# SOC_level_indicator.net
KiCad netlist of a schematic drawn in EAGLE
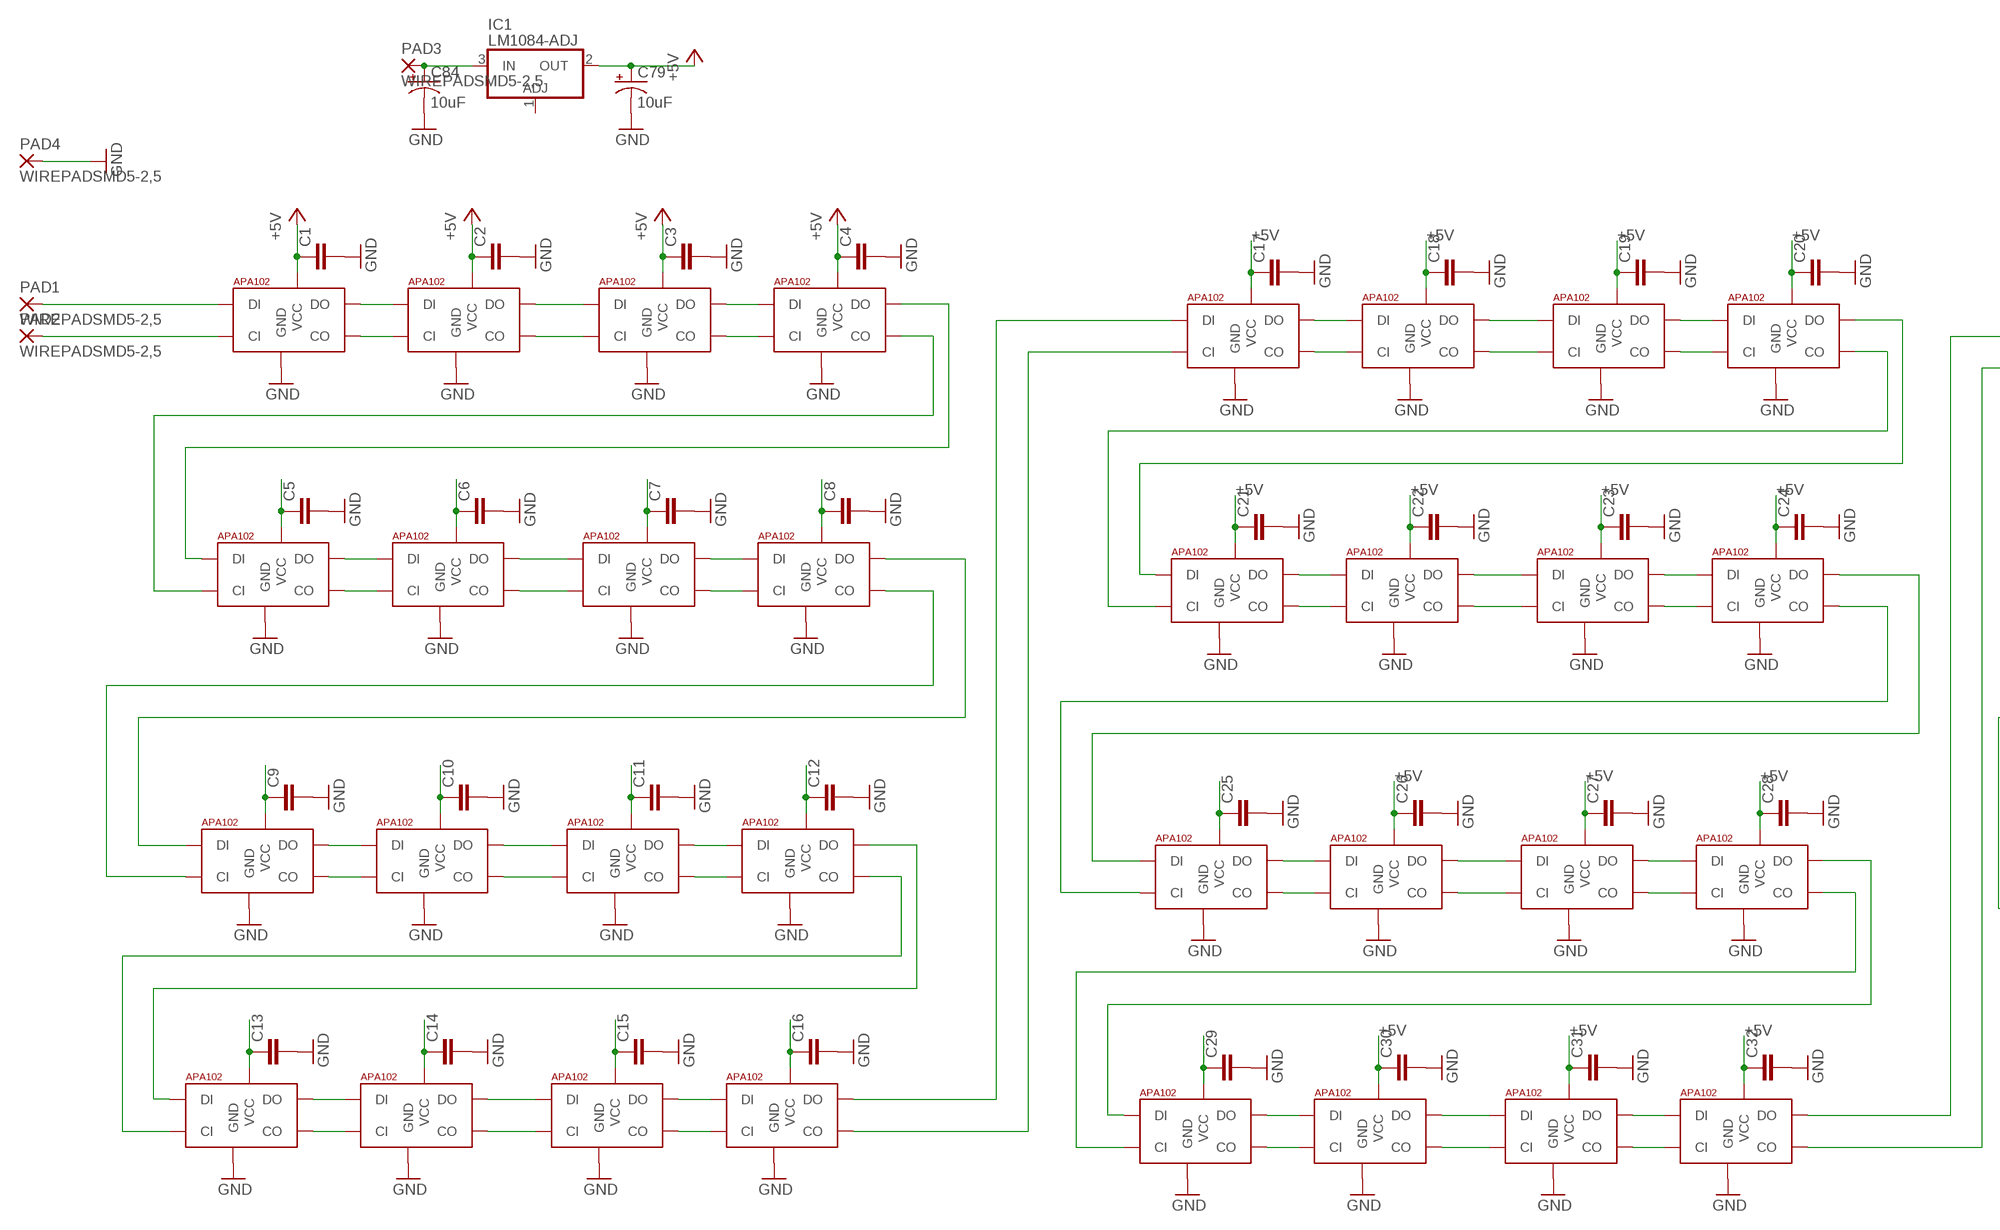
[diagram p0: schematic, sheet 1, part 1 of 2]
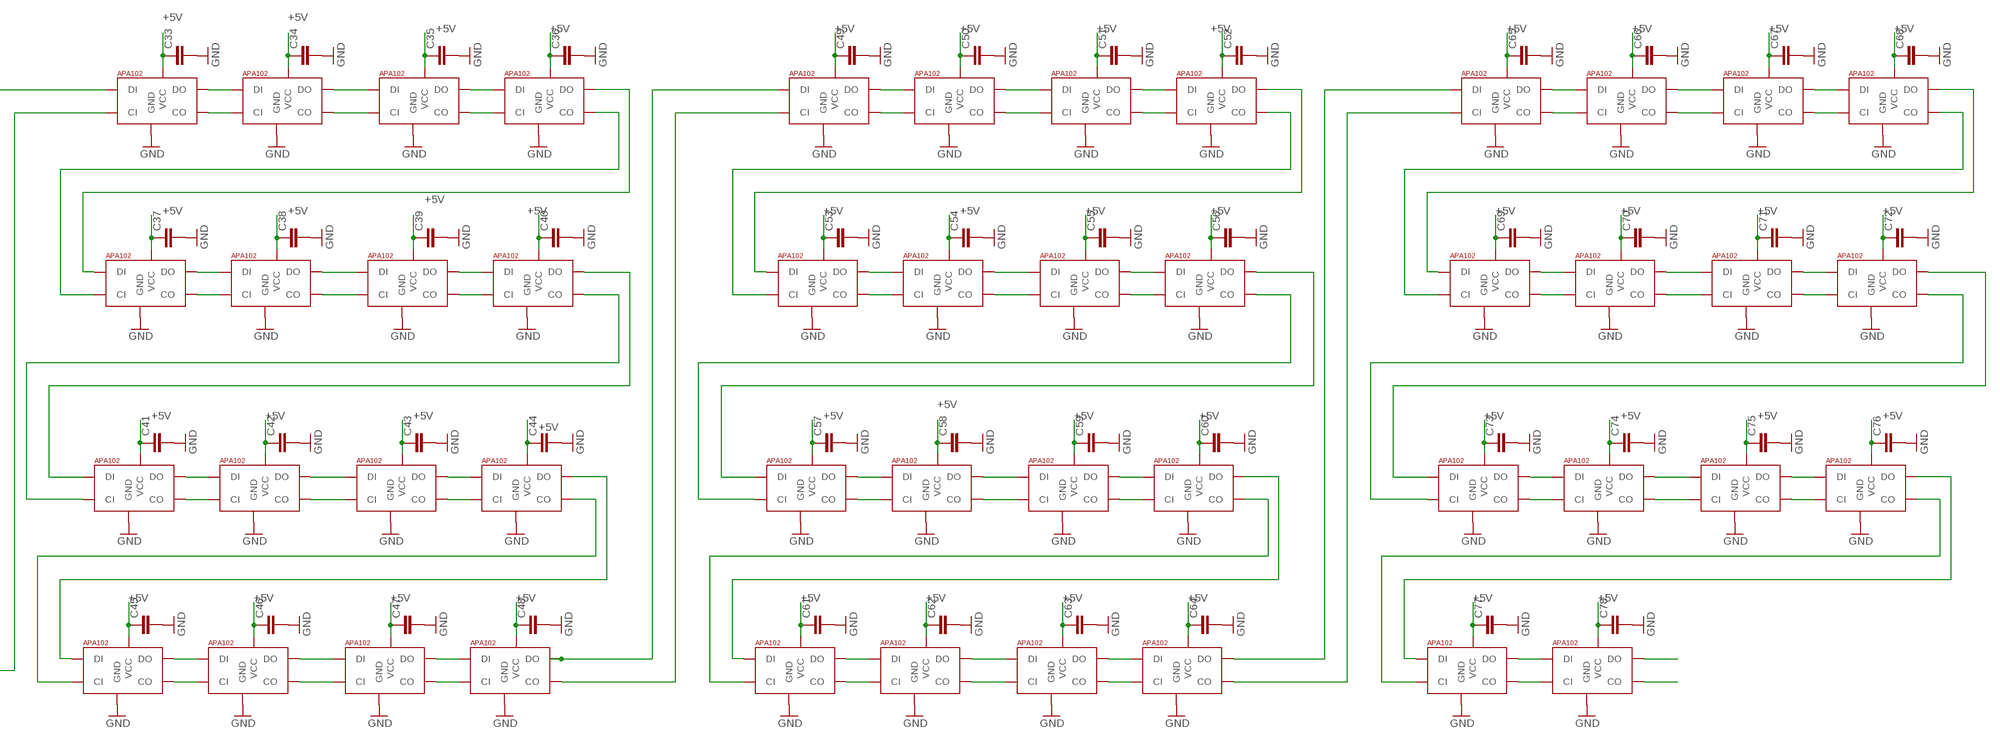
[diagram p1: schematic, sheet 1, part 2 of 2]

(export (version "E")
  (design (tool "Eeschema 10.0.6"))
  (components
    (comp (ref "C1")
      (value "CAP0603-CAP")
      (footprint "eagle-import:0603-CAP")
      (libsource (lib "eagle-import") (part "CAP0603-CAP"))
    )
    (comp (ref "C2")
      (value "CAP0603-CAP")
      (footprint "eagle-import:0603-CAP")
      (libsource (lib "eagle-import") (part "CAP0603-CAP"))
    )
    (comp (ref "C3")
      (value "CAP0603-CAP")
      (footprint "eagle-import:0603-CAP")
      (libsource (lib "eagle-import") (part "CAP0603-CAP"))
    )
    (comp (ref "C4")
      (value "CAP0603-CAP")
      (footprint "eagle-import:0603-CAP")
      (libsource (lib "eagle-import") (part "CAP0603-CAP"))
    )
    (comp (ref "C5")
      (value "CAP0603-CAP")
      (footprint "eagle-import:0603-CAP")
      (libsource (lib "eagle-import") (part "CAP0603-CAP"))
    )
    (comp (ref "C6")
      (value "CAP0603-CAP")
      (footprint "eagle-import:0603-CAP")
      (libsource (lib "eagle-import") (part "CAP0603-CAP"))
    )
    (comp (ref "C7")
      (value "CAP0603-CAP")
      (footprint "eagle-import:0603-CAP")
      (libsource (lib "eagle-import") (part "CAP0603-CAP"))
    )
    (comp (ref "C8")
      (value "CAP0603-CAP")
      (footprint "eagle-import:0603-CAP")
      (libsource (lib "eagle-import") (part "CAP0603-CAP"))
    )
    (comp (ref "C9")
      (value "CAP0603-CAP")
      (footprint "eagle-import:0603-CAP")
      (libsource (lib "eagle-import") (part "CAP0603-CAP"))
    )
    (comp (ref "C10")
      (value "CAP0603-CAP")
      (footprint "eagle-import:0603-CAP")
      (libsource (lib "eagle-import") (part "CAP0603-CAP"))
    )
    (comp (ref "C11")
      (value "CAP0603-CAP")
      (footprint "eagle-import:0603-CAP")
      (libsource (lib "eagle-import") (part "CAP0603-CAP"))
    )
    (comp (ref "C12")
      (value "CAP0603-CAP")
      (footprint "eagle-import:0603-CAP")
      (libsource (lib "eagle-import") (part "CAP0603-CAP"))
    )
    (comp (ref "C13")
      (value "CAP0603-CAP")
      (footprint "eagle-import:0603-CAP")
      (libsource (lib "eagle-import") (part "CAP0603-CAP"))
    )
    (comp (ref "C14")
      (value "CAP0603-CAP")
      (footprint "eagle-import:0603-CAP")
      (libsource (lib "eagle-import") (part "CAP0603-CAP"))
    )
    (comp (ref "C15")
      (value "CAP0603-CAP")
      (footprint "eagle-import:0603-CAP")
      (libsource (lib "eagle-import") (part "CAP0603-CAP"))
    )
    (comp (ref "C16")
      (value "CAP0603-CAP")
      (footprint "eagle-import:0603-CAP")
      (libsource (lib "eagle-import") (part "CAP0603-CAP"))
    )
    (comp (ref "C17")
      (value "CAP0603-CAP")
      (footprint "eagle-import:0603-CAP")
      (libsource (lib "eagle-import") (part "CAP0603-CAP"))
    )
    (comp (ref "C18")
      (value "CAP0603-CAP")
      (footprint "eagle-import:0603-CAP")
      (libsource (lib "eagle-import") (part "CAP0603-CAP"))
    )
    (comp (ref "C19")
      (value "CAP0603-CAP")
      (footprint "eagle-import:0603-CAP")
      (libsource (lib "eagle-import") (part "CAP0603-CAP"))
    )
    (comp (ref "C20")
      (value "CAP0603-CAP")
      (footprint "eagle-import:0603-CAP")
      (libsource (lib "eagle-import") (part "CAP0603-CAP"))
    )
    (comp (ref "C21")
      (value "CAP0603-CAP")
      (footprint "eagle-import:0603-CAP")
      (libsource (lib "eagle-import") (part "CAP0603-CAP"))
    )
    (comp (ref "C22")
      (value "CAP0603-CAP")
      (footprint "eagle-import:0603-CAP")
      (libsource (lib "eagle-import") (part "CAP0603-CAP"))
    )
    (comp (ref "C23")
      (value "CAP0603-CAP")
      (footprint "eagle-import:0603-CAP")
      (libsource (lib "eagle-import") (part "CAP0603-CAP"))
    )
    (comp (ref "C24")
      (value "CAP0603-CAP")
      (footprint "eagle-import:0603-CAP")
      (libsource (lib "eagle-import") (part "CAP0603-CAP"))
    )
    (comp (ref "C25")
      (value "CAP0603-CAP")
      (footprint "eagle-import:0603-CAP")
      (libsource (lib "eagle-import") (part "CAP0603-CAP"))
    )
    (comp (ref "C26")
      (value "CAP0603-CAP")
      (footprint "eagle-import:0603-CAP")
      (libsource (lib "eagle-import") (part "CAP0603-CAP"))
    )
    (comp (ref "C27")
      (value "CAP0603-CAP")
      (footprint "eagle-import:0603-CAP")
      (libsource (lib "eagle-import") (part "CAP0603-CAP"))
    )
    (comp (ref "C28")
      (value "CAP0603-CAP")
      (footprint "eagle-import:0603-CAP")
      (libsource (lib "eagle-import") (part "CAP0603-CAP"))
    )
    (comp (ref "C29")
      (value "CAP0603-CAP")
      (footprint "eagle-import:0603-CAP")
      (libsource (lib "eagle-import") (part "CAP0603-CAP"))
    )
    (comp (ref "C30")
      (value "CAP0603-CAP")
      (footprint "eagle-import:0603-CAP")
      (libsource (lib "eagle-import") (part "CAP0603-CAP"))
    )
    (comp (ref "C31")
      (value "CAP0603-CAP")
      (footprint "eagle-import:0603-CAP")
      (libsource (lib "eagle-import") (part "CAP0603-CAP"))
    )
    (comp (ref "C32")
      (value "CAP0603-CAP")
      (footprint "eagle-import:0603-CAP")
      (libsource (lib "eagle-import") (part "CAP0603-CAP"))
    )
    (comp (ref "C33")
      (value "CAP0603-CAP")
      (footprint "eagle-import:0603-CAP")
      (libsource (lib "eagle-import") (part "CAP0603-CAP"))
    )
    (comp (ref "C34")
      (value "CAP0603-CAP")
      (footprint "eagle-import:0603-CAP")
      (libsource (lib "eagle-import") (part "CAP0603-CAP"))
    )
    (comp (ref "C35")
      (value "CAP0603-CAP")
      (footprint "eagle-import:0603-CAP")
      (libsource (lib "eagle-import") (part "CAP0603-CAP"))
    )
    (comp (ref "C36")
      (value "CAP0603-CAP")
      (footprint "eagle-import:0603-CAP")
      (libsource (lib "eagle-import") (part "CAP0603-CAP"))
    )
    (comp (ref "C37")
      (value "CAP0603-CAP")
      (footprint "eagle-import:0603-CAP")
      (libsource (lib "eagle-import") (part "CAP0603-CAP"))
    )
    (comp (ref "C38")
      (value "CAP0603-CAP")
      (footprint "eagle-import:0603-CAP")
      (libsource (lib "eagle-import") (part "CAP0603-CAP"))
    )
    (comp (ref "C39")
      (value "CAP0603-CAP")
      (footprint "eagle-import:0603-CAP")
      (libsource (lib "eagle-import") (part "CAP0603-CAP"))
    )
    (comp (ref "C40")
      (value "CAP0603-CAP")
      (footprint "eagle-import:0603-CAP")
      (libsource (lib "eagle-import") (part "CAP0603-CAP"))
    )
    (comp (ref "C41")
      (value "CAP0603-CAP")
      (footprint "eagle-import:0603-CAP")
      (libsource (lib "eagle-import") (part "CAP0603-CAP"))
    )
    (comp (ref "C42")
      (value "CAP0603-CAP")
      (footprint "eagle-import:0603-CAP")
      (libsource (lib "eagle-import") (part "CAP0603-CAP"))
    )
    (comp (ref "C43")
      (value "CAP0603-CAP")
      (footprint "eagle-import:0603-CAP")
      (libsource (lib "eagle-import") (part "CAP0603-CAP"))
    )
    (comp (ref "C44")
      (value "CAP0603-CAP")
      (footprint "eagle-import:0603-CAP")
      (libsource (lib "eagle-import") (part "CAP0603-CAP"))
    )
    (comp (ref "C45")
      (value "CAP0603-CAP")
      (footprint "eagle-import:0603-CAP")
      (libsource (lib "eagle-import") (part "CAP0603-CAP"))
    )
    (comp (ref "C46")
      (value "CAP0603-CAP")
      (footprint "eagle-import:0603-CAP")
      (libsource (lib "eagle-import") (part "CAP0603-CAP"))
    )
    (comp (ref "C47")
      (value "CAP0603-CAP")
      (footprint "eagle-import:0603-CAP")
      (libsource (lib "eagle-import") (part "CAP0603-CAP"))
    )
    (comp (ref "C48")
      (value "CAP0603-CAP")
      (footprint "eagle-import:0603-CAP")
      (libsource (lib "eagle-import") (part "CAP0603-CAP"))
    )
    (comp (ref "C49")
      (value "CAP0603-CAP")
      (footprint "eagle-import:0603-CAP")
      (libsource (lib "eagle-import") (part "CAP0603-CAP"))
    )
    (comp (ref "C50")
      (value "CAP0603-CAP")
      (footprint "eagle-import:0603-CAP")
      (libsource (lib "eagle-import") (part "CAP0603-CAP"))
    )
    (comp (ref "C51")
      (value "CAP0603-CAP")
      (footprint "eagle-import:0603-CAP")
      (libsource (lib "eagle-import") (part "CAP0603-CAP"))
    )
    (comp (ref "C52")
      (value "CAP0603-CAP")
      (footprint "eagle-import:0603-CAP")
      (libsource (lib "eagle-import") (part "CAP0603-CAP"))
    )
    (comp (ref "C53")
      (value "CAP0603-CAP")
      (footprint "eagle-import:0603-CAP")
      (libsource (lib "eagle-import") (part "CAP0603-CAP"))
    )
    (comp (ref "C54")
      (value "CAP0603-CAP")
      (footprint "eagle-import:0603-CAP")
      (libsource (lib "eagle-import") (part "CAP0603-CAP"))
    )
    (comp (ref "C55")
      (value "CAP0603-CAP")
      (footprint "eagle-import:0603-CAP")
      (libsource (lib "eagle-import") (part "CAP0603-CAP"))
    )
    (comp (ref "C56")
      (value "CAP0603-CAP")
      (footprint "eagle-import:0603-CAP")
      (libsource (lib "eagle-import") (part "CAP0603-CAP"))
    )
    (comp (ref "C57")
      (value "CAP0603-CAP")
      (footprint "eagle-import:0603-CAP")
      (libsource (lib "eagle-import") (part "CAP0603-CAP"))
    )
    (comp (ref "C58")
      (value "CAP0603-CAP")
      (footprint "eagle-import:0603-CAP")
      (libsource (lib "eagle-import") (part "CAP0603-CAP"))
    )
    (comp (ref "C59")
      (value "CAP0603-CAP")
      (footprint "eagle-import:0603-CAP")
      (libsource (lib "eagle-import") (part "CAP0603-CAP"))
    )
    (comp (ref "C60")
      (value "CAP0603-CAP")
      (footprint "eagle-import:0603-CAP")
      (libsource (lib "eagle-import") (part "CAP0603-CAP"))
    )
    (comp (ref "C61")
      (value "CAP0603-CAP")
      (footprint "eagle-import:0603-CAP")
      (libsource (lib "eagle-import") (part "CAP0603-CAP"))
    )
    (comp (ref "C62")
      (value "CAP0603-CAP")
      (footprint "eagle-import:0603-CAP")
      (libsource (lib "eagle-import") (part "CAP0603-CAP"))
    )
    (comp (ref "C63")
      (value "CAP0603-CAP")
      (footprint "eagle-import:0603-CAP")
      (libsource (lib "eagle-import") (part "CAP0603-CAP"))
    )
    (comp (ref "C64")
      (value "CAP0603-CAP")
      (footprint "eagle-import:0603-CAP")
      (libsource (lib "eagle-import") (part "CAP0603-CAP"))
    )
    (comp (ref "C65")
      (value "CAP0603-CAP")
      (footprint "eagle-import:0603-CAP")
      (libsource (lib "eagle-import") (part "CAP0603-CAP"))
    )
    (comp (ref "C66")
      (value "CAP0603-CAP")
      (footprint "eagle-import:0603-CAP")
      (libsource (lib "eagle-import") (part "CAP0603-CAP"))
    )
    (comp (ref "C67")
      (value "CAP0603-CAP")
      (footprint "eagle-import:0603-CAP")
      (libsource (lib "eagle-import") (part "CAP0603-CAP"))
    )
    (comp (ref "C68")
      (value "CAP0603-CAP")
      (footprint "eagle-import:0603-CAP")
      (libsource (lib "eagle-import") (part "CAP0603-CAP"))
    )
    (comp (ref "C69")
      (value "CAP0603-CAP")
      (footprint "eagle-import:0603-CAP")
      (libsource (lib "eagle-import") (part "CAP0603-CAP"))
    )
    (comp (ref "C70")
      (value "CAP0603-CAP")
      (footprint "eagle-import:0603-CAP")
      (libsource (lib "eagle-import") (part "CAP0603-CAP"))
    )
    (comp (ref "C71")
      (value "CAP0603-CAP")
      (footprint "eagle-import:0603-CAP")
      (libsource (lib "eagle-import") (part "CAP0603-CAP"))
    )
    (comp (ref "C72")
      (value "CAP0603-CAP")
      (footprint "eagle-import:0603-CAP")
      (libsource (lib "eagle-import") (part "CAP0603-CAP"))
    )
    (comp (ref "C73")
      (value "CAP0603-CAP")
      (footprint "eagle-import:0603-CAP")
      (libsource (lib "eagle-import") (part "CAP0603-CAP"))
    )
    (comp (ref "C74")
      (value "CAP0603-CAP")
      (footprint "eagle-import:0603-CAP")
      (libsource (lib "eagle-import") (part "CAP0603-CAP"))
    )
    (comp (ref "C75")
      (value "CAP0603-CAP")
      (footprint "eagle-import:0603-CAP")
      (libsource (lib "eagle-import") (part "CAP0603-CAP"))
    )
    (comp (ref "C76")
      (value "CAP0603-CAP")
      (footprint "eagle-import:0603-CAP")
      (libsource (lib "eagle-import") (part "CAP0603-CAP"))
    )
    (comp (ref "C77")
      (value "CAP0603-CAP")
      (footprint "eagle-import:0603-CAP")
      (libsource (lib "eagle-import") (part "CAP0603-CAP"))
    )
    (comp (ref "C78")
      (value "CAP0603-CAP")
      (footprint "eagle-import:0603-CAP")
      (libsource (lib "eagle-import") (part "CAP0603-CAP"))
    )
    (comp (ref "C79")
      (value "10uF")
      (footprint "eagle-import:EIA3216")
      (libsource (lib "eagle-import") (part "10UF-16V-10%(TANT)"))
    )
    (comp (ref "C84")
      (value "10uF")
      (footprint "eagle-import:EIA3216")
      (libsource (lib "eagle-import") (part "10UF-16V-10%(TANT)"))
    )
    (comp (ref "IC1")
      (value "LM1084-ADJ")
      (footprint "eagle-import:TO263-3")
      (libsource (lib "eagle-import") (part "LM1084-ADJ"))
    )
    (comp (ref "PAD1")
      (value "WIREPADSMD5-2,5")
      (footprint "eagle-import:5-2,5")
      (libsource (lib "eagle-import") (part "WIREPADSMD5-2,5"))
    )
    (comp (ref "PAD2")
      (value "WIREPADSMD5-2,5")
      (footprint "eagle-import:5-2,5")
      (libsource (lib "eagle-import") (part "WIREPADSMD5-2,5"))
    )
    (comp (ref "PAD3")
      (value "WIREPADSMD5-2,5")
      (footprint "eagle-import:5-2,5")
      (libsource (lib "eagle-import") (part "WIREPADSMD5-2,5"))
    )
    (comp (ref "PAD4")
      (value "WIREPADSMD5-2,5")
      (footprint "eagle-import:5-2,5")
      (libsource (lib "eagle-import") (part "WIREPADSMD5-2,5"))
    )
    (comp (ref "U$1")
      (value "APA1025050")
      (footprint "eagle-import:APA102_5050")
      (libsource (lib "eagle-import") (part "APA1025050"))
    )
    (comp (ref "U$2")
      (value "APA1025050")
      (footprint "eagle-import:APA102_5050")
      (libsource (lib "eagle-import") (part "APA1025050"))
    )
    (comp (ref "U$3")
      (value "APA1025050")
      (footprint "eagle-import:APA102_5050")
      (libsource (lib "eagle-import") (part "APA1025050"))
    )
    (comp (ref "U$4")
      (value "APA1025050")
      (footprint "eagle-import:APA102_5050")
      (libsource (lib "eagle-import") (part "APA1025050"))
    )
    (comp (ref "U$5")
      (value "APA1025050")
      (footprint "eagle-import:APA102_5050")
      (libsource (lib "eagle-import") (part "APA1025050"))
    )
    (comp (ref "U$6")
      (value "APA1025050")
      (footprint "eagle-import:APA102_5050")
      (libsource (lib "eagle-import") (part "APA1025050"))
    )
    (comp (ref "U$7")
      (value "APA1025050")
      (footprint "eagle-import:APA102_5050")
      (libsource (lib "eagle-import") (part "APA1025050"))
    )
    (comp (ref "U$8")
      (value "APA1025050")
      (footprint "eagle-import:APA102_5050")
      (libsource (lib "eagle-import") (part "APA1025050"))
    )
    (comp (ref "U$9")
      (value "APA1025050")
      (footprint "eagle-import:APA102_5050")
      (libsource (lib "eagle-import") (part "APA1025050"))
    )
    (comp (ref "U$10")
      (value "APA1025050")
      (footprint "eagle-import:APA102_5050")
      (libsource (lib "eagle-import") (part "APA1025050"))
    )
    (comp (ref "U$11")
      (value "APA1025050")
      (footprint "eagle-import:APA102_5050")
      (libsource (lib "eagle-import") (part "APA1025050"))
    )
    (comp (ref "U$12")
      (value "APA1025050")
      (footprint "eagle-import:APA102_5050")
      (libsource (lib "eagle-import") (part "APA1025050"))
    )
    (comp (ref "U$13")
      (value "APA1025050")
      (footprint "eagle-import:APA102_5050")
      (libsource (lib "eagle-import") (part "APA1025050"))
    )
    (comp (ref "U$14")
      (value "APA1025050")
      (footprint "eagle-import:APA102_5050")
      (libsource (lib "eagle-import") (part "APA1025050"))
    )
    (comp (ref "U$15")
      (value "APA1025050")
      (footprint "eagle-import:APA102_5050")
      (libsource (lib "eagle-import") (part "APA1025050"))
    )
    (comp (ref "U$16")
      (value "APA1025050")
      (footprint "eagle-import:APA102_5050")
      (libsource (lib "eagle-import") (part "APA1025050"))
    )
    (comp (ref "U$17")
      (value "APA1025050")
      (footprint "eagle-import:APA102_5050")
      (libsource (lib "eagle-import") (part "APA1025050"))
    )
    (comp (ref "U$18")
      (value "APA1025050")
      (footprint "eagle-import:APA102_5050")
      (libsource (lib "eagle-import") (part "APA1025050"))
    )
    (comp (ref "U$19")
      (value "APA1025050")
      (footprint "eagle-import:APA102_5050")
      (libsource (lib "eagle-import") (part "APA1025050"))
    )
    (comp (ref "U$20")
      (value "APA1025050")
      (footprint "eagle-import:APA102_5050")
      (libsource (lib "eagle-import") (part "APA1025050"))
    )
    (comp (ref "U$21")
      (value "APA1025050")
      (footprint "eagle-import:APA102_5050")
      (libsource (lib "eagle-import") (part "APA1025050"))
    )
    (comp (ref "U$22")
      (value "APA1025050")
      (footprint "eagle-import:APA102_5050")
      (libsource (lib "eagle-import") (part "APA1025050"))
    )
    (comp (ref "U$23")
      (value "APA1025050")
      (footprint "eagle-import:APA102_5050")
      (libsource (lib "eagle-import") (part "APA1025050"))
    )
    (comp (ref "U$24")
      (value "APA1025050")
      (footprint "eagle-import:APA102_5050")
      (libsource (lib "eagle-import") (part "APA1025050"))
    )
    (comp (ref "U$25")
      (value "APA1025050")
      (footprint "eagle-import:APA102_5050")
      (libsource (lib "eagle-import") (part "APA1025050"))
    )
    (comp (ref "U$26")
      (value "APA1025050")
      (footprint "eagle-import:APA102_5050")
      (libsource (lib "eagle-import") (part "APA1025050"))
    )
    (comp (ref "U$27")
      (value "APA1025050")
      (footprint "eagle-import:APA102_5050")
      (libsource (lib "eagle-import") (part "APA1025050"))
    )
    (comp (ref "U$28")
      (value "APA1025050")
      (footprint "eagle-import:APA102_5050")
      (libsource (lib "eagle-import") (part "APA1025050"))
    )
    (comp (ref "U$29")
      (value "APA1025050")
      (footprint "eagle-import:APA102_5050")
      (libsource (lib "eagle-import") (part "APA1025050"))
    )
    (comp (ref "U$30")
      (value "APA1025050")
      (footprint "eagle-import:APA102_5050")
      (libsource (lib "eagle-import") (part "APA1025050"))
    )
    (comp (ref "U$31")
      (value "APA1025050")
      (footprint "eagle-import:APA102_5050")
      (libsource (lib "eagle-import") (part "APA1025050"))
    )
    (comp (ref "U$32")
      (value "APA1025050")
      (footprint "eagle-import:APA102_5050")
      (libsource (lib "eagle-import") (part "APA1025050"))
    )
    (comp (ref "U$33")
      (value "APA1025050")
      (footprint "eagle-import:APA102_5050")
      (libsource (lib "eagle-import") (part "APA1025050"))
    )
    (comp (ref "U$34")
      (value "APA1025050")
      (footprint "eagle-import:APA102_5050")
      (libsource (lib "eagle-import") (part "APA1025050"))
    )
    (comp (ref "U$35")
      (value "APA1025050")
      (footprint "eagle-import:APA102_5050")
      (libsource (lib "eagle-import") (part "APA1025050"))
    )
    (comp (ref "U$36")
      (value "APA1025050")
      (footprint "eagle-import:APA102_5050")
      (libsource (lib "eagle-import") (part "APA1025050"))
    )
    (comp (ref "U$37")
      (value "APA1025050")
      (footprint "eagle-import:APA102_5050")
      (libsource (lib "eagle-import") (part "APA1025050"))
    )
    (comp (ref "U$38")
      (value "APA1025050")
      (footprint "eagle-import:APA102_5050")
      (libsource (lib "eagle-import") (part "APA1025050"))
    )
    (comp (ref "U$39")
      (value "APA1025050")
      (footprint "eagle-import:APA102_5050")
      (libsource (lib "eagle-import") (part "APA1025050"))
    )
    (comp (ref "U$40")
      (value "APA1025050")
      (footprint "eagle-import:APA102_5050")
      (libsource (lib "eagle-import") (part "APA1025050"))
    )
    (comp (ref "U$41")
      (value "APA1025050")
      (footprint "eagle-import:APA102_5050")
      (libsource (lib "eagle-import") (part "APA1025050"))
    )
    (comp (ref "U$42")
      (value "APA1025050")
      (footprint "eagle-import:APA102_5050")
      (libsource (lib "eagle-import") (part "APA1025050"))
    )
    (comp (ref "U$43")
      (value "APA1025050")
      (footprint "eagle-import:APA102_5050")
      (libsource (lib "eagle-import") (part "APA1025050"))
    )
    (comp (ref "U$44")
      (value "APA1025050")
      (footprint "eagle-import:APA102_5050")
      (libsource (lib "eagle-import") (part "APA1025050"))
    )
    (comp (ref "U$45")
      (value "APA1025050")
      (footprint "eagle-import:APA102_5050")
      (libsource (lib "eagle-import") (part "APA1025050"))
    )
    (comp (ref "U$46")
      (value "APA1025050")
      (footprint "eagle-import:APA102_5050")
      (libsource (lib "eagle-import") (part "APA1025050"))
    )
    (comp (ref "U$47")
      (value "APA1025050")
      (footprint "eagle-import:APA102_5050")
      (libsource (lib "eagle-import") (part "APA1025050"))
    )
    (comp (ref "U$48")
      (value "APA1025050")
      (footprint "eagle-import:APA102_5050")
      (libsource (lib "eagle-import") (part "APA1025050"))
    )
    (comp (ref "U$49")
      (value "APA1025050")
      (footprint "eagle-import:APA102_5050")
      (libsource (lib "eagle-import") (part "APA1025050"))
    )
    (comp (ref "U$50")
      (value "APA1025050")
      (footprint "eagle-import:APA102_5050")
      (libsource (lib "eagle-import") (part "APA1025050"))
    )
    (comp (ref "U$51")
      (value "APA1025050")
      (footprint "eagle-import:APA102_5050")
      (libsource (lib "eagle-import") (part "APA1025050"))
    )
    (comp (ref "U$52")
      (value "APA1025050")
      (footprint "eagle-import:APA102_5050")
      (libsource (lib "eagle-import") (part "APA1025050"))
    )
    (comp (ref "U$53")
      (value "APA1025050")
      (footprint "eagle-import:APA102_5050")
      (libsource (lib "eagle-import") (part "APA1025050"))
    )
    (comp (ref "U$54")
      (value "APA1025050")
      (footprint "eagle-import:APA102_5050")
      (libsource (lib "eagle-import") (part "APA1025050"))
    )
    (comp (ref "U$55")
      (value "APA1025050")
      (footprint "eagle-import:APA102_5050")
      (libsource (lib "eagle-import") (part "APA1025050"))
    )
    (comp (ref "U$56")
      (value "APA1025050")
      (footprint "eagle-import:APA102_5050")
      (libsource (lib "eagle-import") (part "APA1025050"))
    )
    (comp (ref "U$57")
      (value "APA1025050")
      (footprint "eagle-import:APA102_5050")
      (libsource (lib "eagle-import") (part "APA1025050"))
    )
    (comp (ref "U$58")
      (value "APA1025050")
      (footprint "eagle-import:APA102_5050")
      (libsource (lib "eagle-import") (part "APA1025050"))
    )
    (comp (ref "U$59")
      (value "APA1025050")
      (footprint "eagle-import:APA102_5050")
      (libsource (lib "eagle-import") (part "APA1025050"))
    )
    (comp (ref "U$60")
      (value "APA1025050")
      (footprint "eagle-import:APA102_5050")
      (libsource (lib "eagle-import") (part "APA1025050"))
    )
    (comp (ref "U$61")
      (value "APA1025050")
      (footprint "eagle-import:APA102_5050")
      (libsource (lib "eagle-import") (part "APA1025050"))
    )
    (comp (ref "U$62")
      (value "APA1025050")
      (footprint "eagle-import:APA102_5050")
      (libsource (lib "eagle-import") (part "APA1025050"))
    )
    (comp (ref "U$63")
      (value "APA1025050")
      (footprint "eagle-import:APA102_5050")
      (libsource (lib "eagle-import") (part "APA1025050"))
    )
    (comp (ref "U$64")
      (value "APA1025050")
      (footprint "eagle-import:APA102_5050")
      (libsource (lib "eagle-import") (part "APA1025050"))
    )
    (comp (ref "U$65")
      (value "APA1025050")
      (footprint "eagle-import:APA102_5050")
      (libsource (lib "eagle-import") (part "APA1025050"))
    )
    (comp (ref "U$66")
      (value "APA1025050")
      (footprint "eagle-import:APA102_5050")
      (libsource (lib "eagle-import") (part "APA1025050"))
    )
    (comp (ref "U$67")
      (value "APA1025050")
      (footprint "eagle-import:APA102_5050")
      (libsource (lib "eagle-import") (part "APA1025050"))
    )
    (comp (ref "U$68")
      (value "APA1025050")
      (footprint "eagle-import:APA102_5050")
      (libsource (lib "eagle-import") (part "APA1025050"))
    )
    (comp (ref "U$69")
      (value "APA1025050")
      (footprint "eagle-import:APA102_5050")
      (libsource (lib "eagle-import") (part "APA1025050"))
    )
    (comp (ref "U$70")
      (value "APA1025050")
      (footprint "eagle-import:APA102_5050")
      (libsource (lib "eagle-import") (part "APA1025050"))
    )
    (comp (ref "U$71")
      (value "APA1025050")
      (footprint "eagle-import:APA102_5050")
      (libsource (lib "eagle-import") (part "APA1025050"))
    )
    (comp (ref "U$72")
      (value "APA1025050")
      (footprint "eagle-import:APA102_5050")
      (libsource (lib "eagle-import") (part "APA1025050"))
    )
    (comp (ref "U$73")
      (value "APA1025050")
      (footprint "eagle-import:APA102_5050")
      (libsource (lib "eagle-import") (part "APA1025050"))
    )
    (comp (ref "U$74")
      (value "APA1025050")
      (footprint "eagle-import:APA102_5050")
      (libsource (lib "eagle-import") (part "APA1025050"))
    )
    (comp (ref "U$75")
      (value "APA1025050")
      (footprint "eagle-import:APA102_5050")
      (libsource (lib "eagle-import") (part "APA1025050"))
    )
    (comp (ref "U$76")
      (value "APA1025050")
      (footprint "eagle-import:APA102_5050")
      (libsource (lib "eagle-import") (part "APA1025050"))
    )
    (comp (ref "U$77")
      (value "APA1025050")
      (footprint "eagle-import:APA102_5050")
      (libsource (lib "eagle-import") (part "APA1025050"))
    )
    (comp (ref "U$78")
      (value "APA1025050")
      (footprint "eagle-import:APA102_5050")
      (libsource (lib "eagle-import") (part "APA1025050"))
    )
  )
  (nets
    (net (code "1") (name "+5V") (class "Default")
      (node (ref "C1") (pin "1") (pinfunction "1_1") (pintype "passive"))
      (node (ref "C10") (pin "1") (pinfunction "1_1") (pintype "passive"))
      (node (ref "C11") (pin "1") (pinfunction "1_1") (pintype "passive"))
      (node (ref "C12") (pin "1") (pinfunction "1_1") (pintype "passive"))
      (node (ref "C13") (pin "1") (pinfunction "1_1") (pintype "passive"))
      (node (ref "C14") (pin "1") (pinfunction "1_1") (pintype "passive"))
      (node (ref "C15") (pin "1") (pinfunction "1_1") (pintype "passive"))
      (node (ref "C16") (pin "1") (pinfunction "1_1") (pintype "passive"))
      (node (ref "C17") (pin "1") (pinfunction "1_1") (pintype "passive"))
      (node (ref "C18") (pin "1") (pinfunction "1_1") (pintype "passive"))
      (node (ref "C19") (pin "1") (pinfunction "1_1") (pintype "passive"))
      (node (ref "C2") (pin "1") (pinfunction "1_1") (pintype "passive"))
      (node (ref "C20") (pin "1") (pinfunction "1_1") (pintype "passive"))
      (node (ref "C21") (pin "1") (pinfunction "1_1") (pintype "passive"))
      (node (ref "C22") (pin "1") (pinfunction "1_1") (pintype "passive"))
      (node (ref "C23") (pin "1") (pinfunction "1_1") (pintype "passive"))
      (node (ref "C24") (pin "1") (pinfunction "1_1") (pintype "passive"))
      (node (ref "C25") (pin "1") (pinfunction "1_1") (pintype "passive"))
      (node (ref "C26") (pin "1") (pinfunction "1_1") (pintype "passive"))
      (node (ref "C27") (pin "1") (pinfunction "1_1") (pintype "passive"))
      (node (ref "C28") (pin "1") (pinfunction "1_1") (pintype "passive"))
      (node (ref "C29") (pin "1") (pinfunction "1_1") (pintype "passive"))
      (node (ref "C3") (pin "1") (pinfunction "1_1") (pintype "passive"))
      (node (ref "C30") (pin "1") (pinfunction "1_1") (pintype "passive"))
      (node (ref "C31") (pin "1") (pinfunction "1_1") (pintype "passive"))
      (node (ref "C32") (pin "1") (pinfunction "1_1") (pintype "passive"))
      (node (ref "C33") (pin "1") (pinfunction "1_1") (pintype "passive"))
      (node (ref "C34") (pin "1") (pinfunction "1_1") (pintype "passive"))
      (node (ref "C35") (pin "1") (pinfunction "1_1") (pintype "passive"))
      (node (ref "C36") (pin "1") (pinfunction "1_1") (pintype "passive"))
      (node (ref "C37") (pin "1") (pinfunction "1_1") (pintype "passive"))
      (node (ref "C38") (pin "1") (pinfunction "1_1") (pintype "passive"))
      (node (ref "C39") (pin "1") (pinfunction "1_1") (pintype "passive"))
      (node (ref "C4") (pin "1") (pinfunction "1_1") (pintype "passive"))
      (node (ref "C40") (pin "1") (pinfunction "1_1") (pintype "passive"))
      (node (ref "C41") (pin "1") (pinfunction "1_1") (pintype "passive"))
      (node (ref "C42") (pin "1") (pinfunction "1_1") (pintype "passive"))
      (node (ref "C43") (pin "1") (pinfunction "1_1") (pintype "passive"))
      (node (ref "C44") (pin "1") (pinfunction "1_1") (pintype "passive"))
      (node (ref "C45") (pin "1") (pinfunction "1_1") (pintype "passive"))
      (node (ref "C46") (pin "1") (pinfunction "1_1") (pintype "passive"))
      (node (ref "C47") (pin "1") (pinfunction "1_1") (pintype "passive"))
      (node (ref "C48") (pin "1") (pinfunction "1_1") (pintype "passive"))
      (node (ref "C49") (pin "1") (pinfunction "1_1") (pintype "passive"))
      (node (ref "C5") (pin "1") (pinfunction "1_1") (pintype "passive"))
      (node (ref "C50") (pin "1") (pinfunction "1_1") (pintype "passive"))
      (node (ref "C51") (pin "1") (pinfunction "1_1") (pintype "passive"))
      (node (ref "C52") (pin "1") (pinfunction "1_1") (pintype "passive"))
      (node (ref "C53") (pin "1") (pinfunction "1_1") (pintype "passive"))
      (node (ref "C54") (pin "1") (pinfunction "1_1") (pintype "passive"))
      (node (ref "C55") (pin "1") (pinfunction "1_1") (pintype "passive"))
      (node (ref "C56") (pin "1") (pinfunction "1_1") (pintype "passive"))
      (node (ref "C57") (pin "1") (pinfunction "1_1") (pintype "passive"))
      (node (ref "C58") (pin "1") (pinfunction "1_1") (pintype "passive"))
      (node (ref "C59") (pin "1") (pinfunction "1_1") (pintype "passive"))
      (node (ref "C6") (pin "1") (pinfunction "1_1") (pintype "passive"))
      (node (ref "C60") (pin "1") (pinfunction "1_1") (pintype "passive"))
      (node (ref "C61") (pin "1") (pinfunction "1_1") (pintype "passive"))
      (node (ref "C62") (pin "1") (pinfunction "1_1") (pintype "passive"))
      (node (ref "C63") (pin "1") (pinfunction "1_1") (pintype "passive"))
      (node (ref "C64") (pin "1") (pinfunction "1_1") (pintype "passive"))
      (node (ref "C65") (pin "1") (pinfunction "1_1") (pintype "passive"))
      (node (ref "C66") (pin "1") (pinfunction "1_1") (pintype "passive"))
      (node (ref "C67") (pin "1") (pinfunction "1_1") (pintype "passive"))
      (node (ref "C68") (pin "1") (pinfunction "1_1") (pintype "passive"))
      (node (ref "C69") (pin "1") (pinfunction "1_1") (pintype "passive"))
      (node (ref "C7") (pin "1") (pinfunction "1_1") (pintype "passive"))
      (node (ref "C70") (pin "1") (pinfunction "1_1") (pintype "passive"))
      (node (ref "C71") (pin "1") (pinfunction "1_1") (pintype "passive"))
      (node (ref "C72") (pin "1") (pinfunction "1_1") (pintype "passive"))
      (node (ref "C73") (pin "1") (pinfunction "1_1") (pintype "passive"))
      (node (ref "C74") (pin "1") (pinfunction "1_1") (pintype "passive"))
      (node (ref "C75") (pin "1") (pinfunction "1_1") (pintype "passive"))
      (node (ref "C76") (pin "1") (pinfunction "1_1") (pintype "passive"))
      (node (ref "C77") (pin "1") (pinfunction "1_1") (pintype "passive"))
      (node (ref "C78") (pin "1") (pinfunction "1_1") (pintype "passive"))
      (node (ref "C79") (pin "A") (pinfunction "+_A") (pintype "passive"))
      (node (ref "C8") (pin "1") (pinfunction "1_1") (pintype "passive"))
      (node (ref "C9") (pin "1") (pinfunction "1_1") (pintype "passive"))
      (node (ref "IC1") (pin "2") (pinfunction "OUT_2") (pintype "output"))
      (node (ref "U$1") (pin "1") (pinfunction "VCC_1") (pintype "bidirectional"))
      (node (ref "U$10") (pin "1") (pinfunction "VCC_1") (pintype "bidirectional"))
      (node (ref "U$11") (pin "1") (pinfunction "VCC_1") (pintype "bidirectional"))
      (node (ref "U$12") (pin "1") (pinfunction "VCC_1") (pintype "bidirectional"))
      (node (ref "U$13") (pin "1") (pinfunction "VCC_1") (pintype "bidirectional"))
      (node (ref "U$14") (pin "1") (pinfunction "VCC_1") (pintype "bidirectional"))
      (node (ref "U$15") (pin "1") (pinfunction "VCC_1") (pintype "bidirectional"))
      (node (ref "U$16") (pin "1") (pinfunction "VCC_1") (pintype "bidirectional"))
      (node (ref "U$17") (pin "1") (pinfunction "VCC_1") (pintype "bidirectional"))
      (node (ref "U$18") (pin "1") (pinfunction "VCC_1") (pintype "bidirectional"))
      (node (ref "U$19") (pin "1") (pinfunction "VCC_1") (pintype "bidirectional"))
      (node (ref "U$2") (pin "1") (pinfunction "VCC_1") (pintype "bidirectional"))
      (node (ref "U$20") (pin "1") (pinfunction "VCC_1") (pintype "bidirectional"))
      (node (ref "U$21") (pin "1") (pinfunction "VCC_1") (pintype "bidirectional"))
      (node (ref "U$22") (pin "1") (pinfunction "VCC_1") (pintype "bidirectional"))
      (node (ref "U$23") (pin "1") (pinfunction "VCC_1") (pintype "bidirectional"))
      (node (ref "U$24") (pin "1") (pinfunction "VCC_1") (pintype "bidirectional"))
      (node (ref "U$25") (pin "1") (pinfunction "VCC_1") (pintype "bidirectional"))
      (node (ref "U$26") (pin "1") (pinfunction "VCC_1") (pintype "bidirectional"))
      (node (ref "U$27") (pin "1") (pinfunction "VCC_1") (pintype "bidirectional"))
      (node (ref "U$28") (pin "1") (pinfunction "VCC_1") (pintype "bidirectional"))
      (node (ref "U$29") (pin "1") (pinfunction "VCC_1") (pintype "bidirectional"))
      (node (ref "U$3") (pin "1") (pinfunction "VCC_1") (pintype "bidirectional"))
      (node (ref "U$30") (pin "1") (pinfunction "VCC_1") (pintype "bidirectional"))
      (node (ref "U$31") (pin "1") (pinfunction "VCC_1") (pintype "bidirectional"))
      (node (ref "U$32") (pin "1") (pinfunction "VCC_1") (pintype "bidirectional"))
      (node (ref "U$33") (pin "1") (pinfunction "VCC_1") (pintype "bidirectional"))
      (node (ref "U$34") (pin "1") (pinfunction "VCC_1") (pintype "bidirectional"))
      (node (ref "U$35") (pin "1") (pinfunction "VCC_1") (pintype "bidirectional"))
      (node (ref "U$36") (pin "1") (pinfunction "VCC_1") (pintype "bidirectional"))
      (node (ref "U$37") (pin "1") (pinfunction "VCC_1") (pintype "bidirectional"))
      (node (ref "U$38") (pin "1") (pinfunction "VCC_1") (pintype "bidirectional"))
      (node (ref "U$39") (pin "1") (pinfunction "VCC_1") (pintype "bidirectional"))
      (node (ref "U$4") (pin "1") (pinfunction "VCC_1") (pintype "bidirectional"))
      (node (ref "U$40") (pin "1") (pinfunction "VCC_1") (pintype "bidirectional"))
      (node (ref "U$41") (pin "1") (pinfunction "VCC_1") (pintype "bidirectional"))
      (node (ref "U$42") (pin "1") (pinfunction "VCC_1") (pintype "bidirectional"))
      (node (ref "U$43") (pin "1") (pinfunction "VCC_1") (pintype "bidirectional"))
      (node (ref "U$44") (pin "1") (pinfunction "VCC_1") (pintype "bidirectional"))
      (node (ref "U$45") (pin "1") (pinfunction "VCC_1") (pintype "bidirectional"))
      (node (ref "U$46") (pin "1") (pinfunction "VCC_1") (pintype "bidirectional"))
      (node (ref "U$47") (pin "1") (pinfunction "VCC_1") (pintype "bidirectional"))
      (node (ref "U$48") (pin "1") (pinfunction "VCC_1") (pintype "bidirectional"))
      (node (ref "U$49") (pin "1") (pinfunction "VCC_1") (pintype "bidirectional"))
      (node (ref "U$5") (pin "1") (pinfunction "VCC_1") (pintype "bidirectional"))
      (node (ref "U$50") (pin "1") (pinfunction "VCC_1") (pintype "bidirectional"))
      (node (ref "U$51") (pin "1") (pinfunction "VCC_1") (pintype "bidirectional"))
      (node (ref "U$52") (pin "1") (pinfunction "VCC_1") (pintype "bidirectional"))
      (node (ref "U$53") (pin "1") (pinfunction "VCC_1") (pintype "bidirectional"))
      (node (ref "U$54") (pin "1") (pinfunction "VCC_1") (pintype "bidirectional"))
      (node (ref "U$55") (pin "1") (pinfunction "VCC_1") (pintype "bidirectional"))
      (node (ref "U$56") (pin "1") (pinfunction "VCC_1") (pintype "bidirectional"))
      (node (ref "U$57") (pin "1") (pinfunction "VCC_1") (pintype "bidirectional"))
      (node (ref "U$58") (pin "1") (pinfunction "VCC_1") (pintype "bidirectional"))
      (node (ref "U$59") (pin "1") (pinfunction "VCC_1") (pintype "bidirectional"))
      (node (ref "U$6") (pin "1") (pinfunction "VCC_1") (pintype "bidirectional"))
      (node (ref "U$60") (pin "1") (pinfunction "VCC_1") (pintype "bidirectional"))
      (node (ref "U$61") (pin "1") (pinfunction "VCC_1") (pintype "bidirectional"))
      (node (ref "U$62") (pin "1") (pinfunction "VCC_1") (pintype "bidirectional"))
      (node (ref "U$63") (pin "1") (pinfunction "VCC_1") (pintype "bidirectional"))
      (node (ref "U$64") (pin "1") (pinfunction "VCC_1") (pintype "bidirectional"))
      (node (ref "U$65") (pin "1") (pinfunction "VCC_1") (pintype "bidirectional"))
      (node (ref "U$66") (pin "1") (pinfunction "VCC_1") (pintype "bidirectional"))
      (node (ref "U$67") (pin "1") (pinfunction "VCC_1") (pintype "bidirectional"))
      (node (ref "U$68") (pin "1") (pinfunction "VCC_1") (pintype "bidirectional"))
      (node (ref "U$69") (pin "1") (pinfunction "VCC_1") (pintype "bidirectional"))
      (node (ref "U$7") (pin "1") (pinfunction "VCC_1") (pintype "bidirectional"))
      (node (ref "U$70") (pin "1") (pinfunction "VCC_1") (pintype "bidirectional"))
      (node (ref "U$71") (pin "1") (pinfunction "VCC_1") (pintype "bidirectional"))
      (node (ref "U$72") (pin "1") (pinfunction "VCC_1") (pintype "bidirectional"))
      (node (ref "U$73") (pin "1") (pinfunction "VCC_1") (pintype "bidirectional"))
      (node (ref "U$74") (pin "1") (pinfunction "VCC_1") (pintype "bidirectional"))
      (node (ref "U$75") (pin "1") (pinfunction "VCC_1") (pintype "bidirectional"))
      (node (ref "U$76") (pin "1") (pinfunction "VCC_1") (pintype "bidirectional"))
      (node (ref "U$77") (pin "1") (pinfunction "VCC_1") (pintype "bidirectional"))
      (node (ref "U$78") (pin "1") (pinfunction "VCC_1") (pintype "bidirectional"))
      (node (ref "U$8") (pin "1") (pinfunction "VCC_1") (pintype "bidirectional"))
      (node (ref "U$9") (pin "1") (pinfunction "VCC_1") (pintype "bidirectional"))
    )
    (net (code "2") (name "GND") (class "Default")
      (node (ref "C1") (pin "2") (pinfunction "2_2") (pintype "passive"))
      (node (ref "C10") (pin "2") (pinfunction "2_2") (pintype "passive"))
      (node (ref "C11") (pin "2") (pinfunction "2_2") (pintype "passive"))
      (node (ref "C12") (pin "2") (pinfunction "2_2") (pintype "passive"))
      (node (ref "C13") (pin "2") (pinfunction "2_2") (pintype "passive"))
      (node (ref "C14") (pin "2") (pinfunction "2_2") (pintype "passive"))
      (node (ref "C15") (pin "2") (pinfunction "2_2") (pintype "passive"))
      (node (ref "C16") (pin "2") (pinfunction "2_2") (pintype "passive"))
      (node (ref "C17") (pin "2") (pinfunction "2_2") (pintype "passive"))
      (node (ref "C18") (pin "2") (pinfunction "2_2") (pintype "passive"))
      (node (ref "C19") (pin "2") (pinfunction "2_2") (pintype "passive"))
      (node (ref "C2") (pin "2") (pinfunction "2_2") (pintype "passive"))
      (node (ref "C20") (pin "2") (pinfunction "2_2") (pintype "passive"))
      (node (ref "C21") (pin "2") (pinfunction "2_2") (pintype "passive"))
      (node (ref "C22") (pin "2") (pinfunction "2_2") (pintype "passive"))
      (node (ref "C23") (pin "2") (pinfunction "2_2") (pintype "passive"))
      (node (ref "C24") (pin "2") (pinfunction "2_2") (pintype "passive"))
      (node (ref "C25") (pin "2") (pinfunction "2_2") (pintype "passive"))
      (node (ref "C26") (pin "2") (pinfunction "2_2") (pintype "passive"))
      (node (ref "C27") (pin "2") (pinfunction "2_2") (pintype "passive"))
      (node (ref "C28") (pin "2") (pinfunction "2_2") (pintype "passive"))
      (node (ref "C29") (pin "2") (pinfunction "2_2") (pintype "passive"))
      (node (ref "C3") (pin "2") (pinfunction "2_2") (pintype "passive"))
      (node (ref "C30") (pin "2") (pinfunction "2_2") (pintype "passive"))
      (node (ref "C31") (pin "2") (pinfunction "2_2") (pintype "passive"))
      (node (ref "C32") (pin "2") (pinfunction "2_2") (pintype "passive"))
      (node (ref "C33") (pin "2") (pinfunction "2_2") (pintype "passive"))
      (node (ref "C34") (pin "2") (pinfunction "2_2") (pintype "passive"))
      (node (ref "C35") (pin "2") (pinfunction "2_2") (pintype "passive"))
      (node (ref "C36") (pin "2") (pinfunction "2_2") (pintype "passive"))
      (node (ref "C37") (pin "2") (pinfunction "2_2") (pintype "passive"))
      (node (ref "C38") (pin "2") (pinfunction "2_2") (pintype "passive"))
      (node (ref "C39") (pin "2") (pinfunction "2_2") (pintype "passive"))
      (node (ref "C4") (pin "2") (pinfunction "2_2") (pintype "passive"))
      (node (ref "C40") (pin "2") (pinfunction "2_2") (pintype "passive"))
      (node (ref "C41") (pin "2") (pinfunction "2_2") (pintype "passive"))
      (node (ref "C42") (pin "2") (pinfunction "2_2") (pintype "passive"))
      (node (ref "C43") (pin "2") (pinfunction "2_2") (pintype "passive"))
      (node (ref "C44") (pin "2") (pinfunction "2_2") (pintype "passive"))
      (node (ref "C45") (pin "2") (pinfunction "2_2") (pintype "passive"))
      (node (ref "C46") (pin "2") (pinfunction "2_2") (pintype "passive"))
      (node (ref "C47") (pin "2") (pinfunction "2_2") (pintype "passive"))
      (node (ref "C48") (pin "2") (pinfunction "2_2") (pintype "passive"))
      (node (ref "C49") (pin "2") (pinfunction "2_2") (pintype "passive"))
      (node (ref "C5") (pin "2") (pinfunction "2_2") (pintype "passive"))
      (node (ref "C50") (pin "2") (pinfunction "2_2") (pintype "passive"))
      (node (ref "C51") (pin "2") (pinfunction "2_2") (pintype "passive"))
      (node (ref "C52") (pin "2") (pinfunction "2_2") (pintype "passive"))
      (node (ref "C53") (pin "2") (pinfunction "2_2") (pintype "passive"))
      (node (ref "C54") (pin "2") (pinfunction "2_2") (pintype "passive"))
      (node (ref "C55") (pin "2") (pinfunction "2_2") (pintype "passive"))
      (node (ref "C56") (pin "2") (pinfunction "2_2") (pintype "passive"))
      (node (ref "C57") (pin "2") (pinfunction "2_2") (pintype "passive"))
      (node (ref "C58") (pin "2") (pinfunction "2_2") (pintype "passive"))
      (node (ref "C59") (pin "2") (pinfunction "2_2") (pintype "passive"))
      (node (ref "C6") (pin "2") (pinfunction "2_2") (pintype "passive"))
      (node (ref "C60") (pin "2") (pinfunction "2_2") (pintype "passive"))
      (node (ref "C61") (pin "2") (pinfunction "2_2") (pintype "passive"))
      (node (ref "C62") (pin "2") (pinfunction "2_2") (pintype "passive"))
      (node (ref "C63") (pin "2") (pinfunction "2_2") (pintype "passive"))
      (node (ref "C64") (pin "2") (pinfunction "2_2") (pintype "passive"))
      (node (ref "C65") (pin "2") (pinfunction "2_2") (pintype "passive"))
      (node (ref "C66") (pin "2") (pinfunction "2_2") (pintype "passive"))
      (node (ref "C67") (pin "2") (pinfunction "2_2") (pintype "passive"))
      (node (ref "C68") (pin "2") (pinfunction "2_2") (pintype "passive"))
      (node (ref "C69") (pin "2") (pinfunction "2_2") (pintype "passive"))
      (node (ref "C7") (pin "2") (pinfunction "2_2") (pintype "passive"))
      (node (ref "C70") (pin "2") (pinfunction "2_2") (pintype "passive"))
      (node (ref "C71") (pin "2") (pinfunction "2_2") (pintype "passive"))
      (node (ref "C72") (pin "2") (pinfunction "2_2") (pintype "passive"))
      (node (ref "C73") (pin "2") (pinfunction "2_2") (pintype "passive"))
      (node (ref "C74") (pin "2") (pinfunction "2_2") (pintype "passive"))
      (node (ref "C75") (pin "2") (pinfunction "2_2") (pintype "passive"))
      (node (ref "C76") (pin "2") (pinfunction "2_2") (pintype "passive"))
      (node (ref "C77") (pin "2") (pinfunction "2_2") (pintype "passive"))
      (node (ref "C78") (pin "2") (pinfunction "2_2") (pintype "passive"))
      (node (ref "C79") (pin "C") (pinfunction "-_C") (pintype "passive"))
      (node (ref "C8") (pin "2") (pinfunction "2_2") (pintype "passive"))
      (node (ref "C84") (pin "C") (pinfunction "-_C") (pintype "passive"))
      (node (ref "C9") (pin "2") (pinfunction "2_2") (pintype "passive"))
      (node (ref "PAD4") (pin "1") (pinfunction "P_1") (pintype "passive"))
      (node (ref "U$1") (pin "6") (pinfunction "GND_6") (pintype "bidirectional"))
      (node (ref "U$10") (pin "6") (pinfunction "GND_6") (pintype "bidirectional"))
      (node (ref "U$11") (pin "6") (pinfunction "GND_6") (pintype "bidirectional"))
      (node (ref "U$12") (pin "6") (pinfunction "GND_6") (pintype "bidirectional"))
      (node (ref "U$13") (pin "6") (pinfunction "GND_6") (pintype "bidirectional"))
      (node (ref "U$14") (pin "6") (pinfunction "GND_6") (pintype "bidirectional"))
      (node (ref "U$15") (pin "6") (pinfunction "GND_6") (pintype "bidirectional"))
      (node (ref "U$16") (pin "6") (pinfunction "GND_6") (pintype "bidirectional"))
      (node (ref "U$17") (pin "6") (pinfunction "GND_6") (pintype "bidirectional"))
      (node (ref "U$18") (pin "6") (pinfunction "GND_6") (pintype "bidirectional"))
      (node (ref "U$19") (pin "6") (pinfunction "GND_6") (pintype "bidirectional"))
      (node (ref "U$2") (pin "6") (pinfunction "GND_6") (pintype "bidirectional"))
      (node (ref "U$20") (pin "6") (pinfunction "GND_6") (pintype "bidirectional"))
      (node (ref "U$21") (pin "6") (pinfunction "GND_6") (pintype "bidirectional"))
      (node (ref "U$22") (pin "6") (pinfunction "GND_6") (pintype "bidirectional"))
      (node (ref "U$23") (pin "6") (pinfunction "GND_6") (pintype "bidirectional"))
      (node (ref "U$24") (pin "6") (pinfunction "GND_6") (pintype "bidirectional"))
      (node (ref "U$25") (pin "6") (pinfunction "GND_6") (pintype "bidirectional"))
      (node (ref "U$26") (pin "6") (pinfunction "GND_6") (pintype "bidirectional"))
      (node (ref "U$27") (pin "6") (pinfunction "GND_6") (pintype "bidirectional"))
      (node (ref "U$28") (pin "6") (pinfunction "GND_6") (pintype "bidirectional"))
      (node (ref "U$29") (pin "6") (pinfunction "GND_6") (pintype "bidirectional"))
      (node (ref "U$3") (pin "6") (pinfunction "GND_6") (pintype "bidirectional"))
      (node (ref "U$30") (pin "6") (pinfunction "GND_6") (pintype "bidirectional"))
      (node (ref "U$31") (pin "6") (pinfunction "GND_6") (pintype "bidirectional"))
      (node (ref "U$32") (pin "6") (pinfunction "GND_6") (pintype "bidirectional"))
      (node (ref "U$33") (pin "6") (pinfunction "GND_6") (pintype "bidirectional"))
      (node (ref "U$34") (pin "6") (pinfunction "GND_6") (pintype "bidirectional"))
      (node (ref "U$35") (pin "6") (pinfunction "GND_6") (pintype "bidirectional"))
      (node (ref "U$36") (pin "6") (pinfunction "GND_6") (pintype "bidirectional"))
      (node (ref "U$37") (pin "6") (pinfunction "GND_6") (pintype "bidirectional"))
      (node (ref "U$38") (pin "6") (pinfunction "GND_6") (pintype "bidirectional"))
      (node (ref "U$39") (pin "6") (pinfunction "GND_6") (pintype "bidirectional"))
      (node (ref "U$4") (pin "6") (pinfunction "GND_6") (pintype "bidirectional"))
      (node (ref "U$40") (pin "6") (pinfunction "GND_6") (pintype "bidirectional"))
      (node (ref "U$41") (pin "6") (pinfunction "GND_6") (pintype "bidirectional"))
      (node (ref "U$42") (pin "6") (pinfunction "GND_6") (pintype "bidirectional"))
      (node (ref "U$43") (pin "6") (pinfunction "GND_6") (pintype "bidirectional"))
      (node (ref "U$44") (pin "6") (pinfunction "GND_6") (pintype "bidirectional"))
      (node (ref "U$45") (pin "6") (pinfunction "GND_6") (pintype "bidirectional"))
      (node (ref "U$46") (pin "6") (pinfunction "GND_6") (pintype "bidirectional"))
      (node (ref "U$47") (pin "6") (pinfunction "GND_6") (pintype "bidirectional"))
      (node (ref "U$48") (pin "6") (pinfunction "GND_6") (pintype "bidirectional"))
      (node (ref "U$49") (pin "6") (pinfunction "GND_6") (pintype "bidirectional"))
      (node (ref "U$5") (pin "6") (pinfunction "GND_6") (pintype "bidirectional"))
      (node (ref "U$50") (pin "6") (pinfunction "GND_6") (pintype "bidirectional"))
      (node (ref "U$51") (pin "6") (pinfunction "GND_6") (pintype "bidirectional"))
      (node (ref "U$52") (pin "6") (pinfunction "GND_6") (pintype "bidirectional"))
      (node (ref "U$53") (pin "6") (pinfunction "GND_6") (pintype "bidirectional"))
      (node (ref "U$54") (pin "6") (pinfunction "GND_6") (pintype "bidirectional"))
      (node (ref "U$55") (pin "6") (pinfunction "GND_6") (pintype "bidirectional"))
      (node (ref "U$56") (pin "6") (pinfunction "GND_6") (pintype "bidirectional"))
      (node (ref "U$57") (pin "6") (pinfunction "GND_6") (pintype "bidirectional"))
      (node (ref "U$58") (pin "6") (pinfunction "GND_6") (pintype "bidirectional"))
      (node (ref "U$59") (pin "6") (pinfunction "GND_6") (pintype "bidirectional"))
      (node (ref "U$6") (pin "6") (pinfunction "GND_6") (pintype "bidirectional"))
      (node (ref "U$60") (pin "6") (pinfunction "GND_6") (pintype "bidirectional"))
      (node (ref "U$61") (pin "6") (pinfunction "GND_6") (pintype "bidirectional"))
      (node (ref "U$62") (pin "6") (pinfunction "GND_6") (pintype "bidirectional"))
      (node (ref "U$63") (pin "6") (pinfunction "GND_6") (pintype "bidirectional"))
      (node (ref "U$64") (pin "6") (pinfunction "GND_6") (pintype "bidirectional"))
      (node (ref "U$65") (pin "6") (pinfunction "GND_6") (pintype "bidirectional"))
      (node (ref "U$66") (pin "6") (pinfunction "GND_6") (pintype "bidirectional"))
      (node (ref "U$67") (pin "6") (pinfunction "GND_6") (pintype "bidirectional"))
      (node (ref "U$68") (pin "6") (pinfunction "GND_6") (pintype "bidirectional"))
      (node (ref "U$69") (pin "6") (pinfunction "GND_6") (pintype "bidirectional"))
      (node (ref "U$7") (pin "6") (pinfunction "GND_6") (pintype "bidirectional"))
      (node (ref "U$70") (pin "6") (pinfunction "GND_6") (pintype "bidirectional"))
      (node (ref "U$71") (pin "6") (pinfunction "GND_6") (pintype "bidirectional"))
      (node (ref "U$72") (pin "6") (pinfunction "GND_6") (pintype "bidirectional"))
      (node (ref "U$73") (pin "6") (pinfunction "GND_6") (pintype "bidirectional"))
      (node (ref "U$74") (pin "6") (pinfunction "GND_6") (pintype "bidirectional"))
      (node (ref "U$75") (pin "6") (pinfunction "GND_6") (pintype "bidirectional"))
      (node (ref "U$76") (pin "6") (pinfunction "GND_6") (pintype "bidirectional"))
      (node (ref "U$77") (pin "6") (pinfunction "GND_6") (pintype "bidirectional"))
      (node (ref "U$78") (pin "6") (pinfunction "GND_6") (pintype "bidirectional"))
      (node (ref "U$8") (pin "6") (pinfunction "GND_6") (pintype "bidirectional"))
      (node (ref "U$9") (pin "6") (pinfunction "GND_6") (pintype "bidirectional"))
    )
    (net (code "3") (name "Net-(C84-+)") (class "Default")
      (node (ref "C84") (pin "A") (pinfunction "+_A") (pintype "passive"))
      (node (ref "IC1") (pin "3") (pinfunction "IN_3") (pintype "input"))
      (node (ref "PAD3") (pin "1") (pinfunction "P_1") (pintype "passive"))
    )
    (net (code "4") (name "Net-(PAD1-P)") (class "Default")
      (node (ref "PAD1") (pin "1") (pinfunction "P_1") (pintype "passive"))
      (node (ref "U$1") (pin "4") (pinfunction "DI_4") (pintype "bidirectional"))
    )
    (net (code "5") (name "Net-(PAD2-P)") (class "Default")
      (node (ref "PAD2") (pin "1") (pinfunction "P_1") (pintype "passive"))
      (node (ref "U$1") (pin "5") (pinfunction "CI_5") (pintype "bidirectional"))
    )
    (net (code "6") (name "Net-(U$1-CO)") (class "Default")
      (node (ref "U$1") (pin "2") (pinfunction "CO_2") (pintype "bidirectional"))
      (node (ref "U$2") (pin "5") (pinfunction "CI_5") (pintype "bidirectional"))
    )
    (net (code "7") (name "Net-(U$1-DO)") (class "Default")
      (node (ref "U$1") (pin "3") (pinfunction "DO_3") (pintype "bidirectional"))
      (node (ref "U$2") (pin "4") (pinfunction "DI_4") (pintype "bidirectional"))
    )
    (net (code "8") (name "Net-(U$2-CO)") (class "Default")
      (node (ref "U$2") (pin "2") (pinfunction "CO_2") (pintype "bidirectional"))
      (node (ref "U$3") (pin "5") (pinfunction "CI_5") (pintype "bidirectional"))
    )
    (net (code "9") (name "Net-(U$2-DO)") (class "Default")
      (node (ref "U$2") (pin "3") (pinfunction "DO_3") (pintype "bidirectional"))
      (node (ref "U$3") (pin "4") (pinfunction "DI_4") (pintype "bidirectional"))
    )
    (net (code "10") (name "Net-(U$3-CO)") (class "Default")
      (node (ref "U$3") (pin "2") (pinfunction "CO_2") (pintype "bidirectional"))
      (node (ref "U$4") (pin "5") (pinfunction "CI_5") (pintype "bidirectional"))
    )
    (net (code "11") (name "Net-(U$3-DO)") (class "Default")
      (node (ref "U$3") (pin "3") (pinfunction "DO_3") (pintype "bidirectional"))
      (node (ref "U$4") (pin "4") (pinfunction "DI_4") (pintype "bidirectional"))
    )
    (net (code "12") (name "Net-(U$4-CO)") (class "Default")
      (node (ref "U$4") (pin "2") (pinfunction "CO_2") (pintype "bidirectional"))
      (node (ref "U$5") (pin "5") (pinfunction "CI_5") (pintype "bidirectional"))
    )
    (net (code "13") (name "Net-(U$4-DO)") (class "Default")
      (node (ref "U$4") (pin "3") (pinfunction "DO_3") (pintype "bidirectional"))
      (node (ref "U$5") (pin "4") (pinfunction "DI_4") (pintype "bidirectional"))
    )
    (net (code "14") (name "Net-(U$5-CO)") (class "Default")
      (node (ref "U$5") (pin "2") (pinfunction "CO_2") (pintype "bidirectional"))
      (node (ref "U$6") (pin "5") (pinfunction "CI_5") (pintype "bidirectional"))
    )
    (net (code "15") (name "Net-(U$5-DO)") (class "Default")
      (node (ref "U$5") (pin "3") (pinfunction "DO_3") (pintype "bidirectional"))
      (node (ref "U$6") (pin "4") (pinfunction "DI_4") (pintype "bidirectional"))
    )
    (net (code "16") (name "Net-(U$6-CO)") (class "Default")
      (node (ref "U$6") (pin "2") (pinfunction "CO_2") (pintype "bidirectional"))
      (node (ref "U$7") (pin "5") (pinfunction "CI_5") (pintype "bidirectional"))
    )
    (net (code "17") (name "Net-(U$6-DO)") (class "Default")
      (node (ref "U$6") (pin "3") (pinfunction "DO_3") (pintype "bidirectional"))
      (node (ref "U$7") (pin "4") (pinfunction "DI_4") (pintype "bidirectional"))
    )
    (net (code "18") (name "Net-(U$7-CO)") (class "Default")
      (node (ref "U$7") (pin "2") (pinfunction "CO_2") (pintype "bidirectional"))
      (node (ref "U$8") (pin "5") (pinfunction "CI_5") (pintype "bidirectional"))
    )
    (net (code "19") (name "Net-(U$7-DO)") (class "Default")
      (node (ref "U$7") (pin "3") (pinfunction "DO_3") (pintype "bidirectional"))
      (node (ref "U$8") (pin "4") (pinfunction "DI_4") (pintype "bidirectional"))
    )
    (net (code "20") (name "Net-(U$8-CO)") (class "Default")
      (node (ref "U$8") (pin "2") (pinfunction "CO_2") (pintype "bidirectional"))
      (node (ref "U$9") (pin "5") (pinfunction "CI_5") (pintype "bidirectional"))
    )
    (net (code "21") (name "Net-(U$8-DO)") (class "Default")
      (node (ref "U$8") (pin "3") (pinfunction "DO_3") (pintype "bidirectional"))
      (node (ref "U$9") (pin "4") (pinfunction "DI_4") (pintype "bidirectional"))
    )
    (net (code "22") (name "Net-(U$10-CI)") (class "Default")
      (node (ref "U$10") (pin "5") (pinfunction "CI_5") (pintype "bidirectional"))
      (node (ref "U$9") (pin "2") (pinfunction "CO_2") (pintype "bidirectional"))
    )
    (net (code "23") (name "Net-(U$10-CO)") (class "Default")
      (node (ref "U$10") (pin "2") (pinfunction "CO_2") (pintype "bidirectional"))
      (node (ref "U$11") (pin "5") (pinfunction "CI_5") (pintype "bidirectional"))
    )
    (net (code "24") (name "Net-(U$10-DI)") (class "Default")
      (node (ref "U$10") (pin "4") (pinfunction "DI_4") (pintype "bidirectional"))
      (node (ref "U$9") (pin "3") (pinfunction "DO_3") (pintype "bidirectional"))
    )
    (net (code "25") (name "Net-(U$10-DO)") (class "Default")
      (node (ref "U$10") (pin "3") (pinfunction "DO_3") (pintype "bidirectional"))
      (node (ref "U$11") (pin "4") (pinfunction "DI_4") (pintype "bidirectional"))
    )
    (net (code "26") (name "Net-(U$11-CO)") (class "Default")
      (node (ref "U$11") (pin "2") (pinfunction "CO_2") (pintype "bidirectional"))
      (node (ref "U$12") (pin "5") (pinfunction "CI_5") (pintype "bidirectional"))
    )
    (net (code "27") (name "Net-(U$11-DO)") (class "Default")
      (node (ref "U$11") (pin "3") (pinfunction "DO_3") (pintype "bidirectional"))
      (node (ref "U$12") (pin "4") (pinfunction "DI_4") (pintype "bidirectional"))
    )
    (net (code "28") (name "Net-(U$12-CO)") (class "Default")
      (node (ref "U$12") (pin "2") (pinfunction "CO_2") (pintype "bidirectional"))
      (node (ref "U$13") (pin "5") (pinfunction "CI_5") (pintype "bidirectional"))
    )
    (net (code "29") (name "Net-(U$12-DO)") (class "Default")
      (node (ref "U$12") (pin "3") (pinfunction "DO_3") (pintype "bidirectional"))
      (node (ref "U$13") (pin "4") (pinfunction "DI_4") (pintype "bidirectional"))
    )
    (net (code "30") (name "Net-(U$13-CO)") (class "Default")
      (node (ref "U$13") (pin "2") (pinfunction "CO_2") (pintype "bidirectional"))
      (node (ref "U$14") (pin "5") (pinfunction "CI_5") (pintype "bidirectional"))
    )
    (net (code "31") (name "Net-(U$13-DO)") (class "Default")
      (node (ref "U$13") (pin "3") (pinfunction "DO_3") (pintype "bidirectional"))
      (node (ref "U$14") (pin "4") (pinfunction "DI_4") (pintype "bidirectional"))
    )
    (net (code "32") (name "Net-(U$14-CO)") (class "Default")
      (node (ref "U$14") (pin "2") (pinfunction "CO_2") (pintype "bidirectional"))
      (node (ref "U$15") (pin "5") (pinfunction "CI_5") (pintype "bidirectional"))
    )
    (net (code "33") (name "Net-(U$14-DO)") (class "Default")
      (node (ref "U$14") (pin "3") (pinfunction "DO_3") (pintype "bidirectional"))
      (node (ref "U$15") (pin "4") (pinfunction "DI_4") (pintype "bidirectional"))
    )
    (net (code "34") (name "Net-(U$15-CO)") (class "Default")
      (node (ref "U$15") (pin "2") (pinfunction "CO_2") (pintype "bidirectional"))
      (node (ref "U$16") (pin "5") (pinfunction "CI_5") (pintype "bidirectional"))
    )
    (net (code "35") (name "Net-(U$15-DO)") (class "Default")
      (node (ref "U$15") (pin "3") (pinfunction "DO_3") (pintype "bidirectional"))
      (node (ref "U$16") (pin "4") (pinfunction "DI_4") (pintype "bidirectional"))
    )
    (net (code "36") (name "Net-(U$16-CO)") (class "Default")
      (node (ref "U$16") (pin "2") (pinfunction "CO_2") (pintype "bidirectional"))
      (node (ref "U$17") (pin "5") (pinfunction "CI_5") (pintype "bidirectional"))
    )
    (net (code "37") (name "Net-(U$16-DO)") (class "Default")
      (node (ref "U$16") (pin "3") (pinfunction "DO_3") (pintype "bidirectional"))
      (node (ref "U$17") (pin "4") (pinfunction "DI_4") (pintype "bidirectional"))
    )
    (net (code "38") (name "Net-(U$17-CO)") (class "Default")
      (node (ref "U$17") (pin "2") (pinfunction "CO_2") (pintype "bidirectional"))
      (node (ref "U$18") (pin "5") (pinfunction "CI_5") (pintype "bidirectional"))
    )
    (net (code "39") (name "Net-(U$17-DO)") (class "Default")
      (node (ref "U$17") (pin "3") (pinfunction "DO_3") (pintype "bidirectional"))
      (node (ref "U$18") (pin "4") (pinfunction "DI_4") (pintype "bidirectional"))
    )
    (net (code "40") (name "Net-(U$18-CO)") (class "Default")
      (node (ref "U$18") (pin "2") (pinfunction "CO_2") (pintype "bidirectional"))
      (node (ref "U$19") (pin "5") (pinfunction "CI_5") (pintype "bidirectional"))
    )
    (net (code "41") (name "Net-(U$18-DO)") (class "Default")
      (node (ref "U$18") (pin "3") (pinfunction "DO_3") (pintype "bidirectional"))
      (node (ref "U$19") (pin "4") (pinfunction "DI_4") (pintype "bidirectional"))
    )
    (net (code "42") (name "Net-(U$19-CO)") (class "Default")
      (node (ref "U$19") (pin "2") (pinfunction "CO_2") (pintype "bidirectional"))
      (node (ref "U$20") (pin "5") (pinfunction "CI_5") (pintype "bidirectional"))
    )
    (net (code "43") (name "Net-(U$19-DO)") (class "Default")
      (node (ref "U$19") (pin "3") (pinfunction "DO_3") (pintype "bidirectional"))
      (node (ref "U$20") (pin "4") (pinfunction "DI_4") (pintype "bidirectional"))
    )
    (net (code "44") (name "Net-(U$20-CO)") (class "Default")
      (node (ref "U$20") (pin "2") (pinfunction "CO_2") (pintype "bidirectional"))
      (node (ref "U$21") (pin "5") (pinfunction "CI_5") (pintype "bidirectional"))
    )
    (net (code "45") (name "Net-(U$20-DO)") (class "Default")
      (node (ref "U$20") (pin "3") (pinfunction "DO_3") (pintype "bidirectional"))
      (node (ref "U$21") (pin "4") (pinfunction "DI_4") (pintype "bidirectional"))
    )
    (net (code "46") (name "Net-(U$21-CO)") (class "Default")
      (node (ref "U$21") (pin "2") (pinfunction "CO_2") (pintype "bidirectional"))
      (node (ref "U$22") (pin "5") (pinfunction "CI_5") (pintype "bidirectional"))
    )
    (net (code "47") (name "Net-(U$21-DO)") (class "Default")
      (node (ref "U$21") (pin "3") (pinfunction "DO_3") (pintype "bidirectional"))
      (node (ref "U$22") (pin "4") (pinfunction "DI_4") (pintype "bidirectional"))
    )
    (net (code "48") (name "Net-(U$22-CO)") (class "Default")
      (node (ref "U$22") (pin "2") (pinfunction "CO_2") (pintype "bidirectional"))
      (node (ref "U$23") (pin "5") (pinfunction "CI_5") (pintype "bidirectional"))
    )
    (net (code "49") (name "Net-(U$22-DO)") (class "Default")
      (node (ref "U$22") (pin "3") (pinfunction "DO_3") (pintype "bidirectional"))
      (node (ref "U$23") (pin "4") (pinfunction "DI_4") (pintype "bidirectional"))
    )
    (net (code "50") (name "Net-(U$23-CO)") (class "Default")
      (node (ref "U$23") (pin "2") (pinfunction "CO_2") (pintype "bidirectional"))
      (node (ref "U$24") (pin "5") (pinfunction "CI_5") (pintype "bidirectional"))
    )
    (net (code "51") (name "Net-(U$23-DO)") (class "Default")
      (node (ref "U$23") (pin "3") (pinfunction "DO_3") (pintype "bidirectional"))
      (node (ref "U$24") (pin "4") (pinfunction "DI_4") (pintype "bidirectional"))
    )
    (net (code "52") (name "Net-(U$24-CO)") (class "Default")
      (node (ref "U$24") (pin "2") (pinfunction "CO_2") (pintype "bidirectional"))
      (node (ref "U$25") (pin "5") (pinfunction "CI_5") (pintype "bidirectional"))
    )
    (net (code "53") (name "Net-(U$24-DO)") (class "Default")
      (node (ref "U$24") (pin "3") (pinfunction "DO_3") (pintype "bidirectional"))
      (node (ref "U$25") (pin "4") (pinfunction "DI_4") (pintype "bidirectional"))
    )
    (net (code "54") (name "Net-(U$25-CO)") (class "Default")
      (node (ref "U$25") (pin "2") (pinfunction "CO_2") (pintype "bidirectional"))
      (node (ref "U$26") (pin "5") (pinfunction "CI_5") (pintype "bidirectional"))
    )
    (net (code "55") (name "Net-(U$25-DO)") (class "Default")
      (node (ref "U$25") (pin "3") (pinfunction "DO_3") (pintype "bidirectional"))
      (node (ref "U$26") (pin "4") (pinfunction "DI_4") (pintype "bidirectional"))
    )
    (net (code "56") (name "Net-(U$26-CO)") (class "Default")
      (node (ref "U$26") (pin "2") (pinfunction "CO_2") (pintype "bidirectional"))
      (node (ref "U$27") (pin "5") (pinfunction "CI_5") (pintype "bidirectional"))
    )
    (net (code "57") (name "Net-(U$26-DO)") (class "Default")
      (node (ref "U$26") (pin "3") (pinfunction "DO_3") (pintype "bidirectional"))
      (node (ref "U$27") (pin "4") (pinfunction "DI_4") (pintype "bidirectional"))
    )
    (net (code "58") (name "Net-(U$27-CO)") (class "Default")
      (node (ref "U$27") (pin "2") (pinfunction "CO_2") (pintype "bidirectional"))
      (node (ref "U$28") (pin "5") (pinfunction "CI_5") (pintype "bidirectional"))
    )
    (net (code "59") (name "Net-(U$27-DO)") (class "Default")
      (node (ref "U$27") (pin "3") (pinfunction "DO_3") (pintype "bidirectional"))
      (node (ref "U$28") (pin "4") (pinfunction "DI_4") (pintype "bidirectional"))
    )
    (net (code "60") (name "Net-(U$28-CO)") (class "Default")
      (node (ref "U$28") (pin "2") (pinfunction "CO_2") (pintype "bidirectional"))
      (node (ref "U$29") (pin "5") (pinfunction "CI_5") (pintype "bidirectional"))
    )
    (net (code "61") (name "Net-(U$28-DO)") (class "Default")
      (node (ref "U$28") (pin "3") (pinfunction "DO_3") (pintype "bidirectional"))
      (node (ref "U$29") (pin "4") (pinfunction "DI_4") (pintype "bidirectional"))
    )
    (net (code "62") (name "Net-(U$29-CO)") (class "Default")
      (node (ref "U$29") (pin "2") (pinfunction "CO_2") (pintype "bidirectional"))
      (node (ref "U$30") (pin "5") (pinfunction "CI_5") (pintype "bidirectional"))
    )
    (net (code "63") (name "Net-(U$29-DO)") (class "Default")
      (node (ref "U$29") (pin "3") (pinfunction "DO_3") (pintype "bidirectional"))
      (node (ref "U$30") (pin "4") (pinfunction "DI_4") (pintype "bidirectional"))
    )
    (net (code "64") (name "Net-(U$30-CO)") (class "Default")
      (node (ref "U$30") (pin "2") (pinfunction "CO_2") (pintype "bidirectional"))
      (node (ref "U$31") (pin "5") (pinfunction "CI_5") (pintype "bidirectional"))
    )
    (net (code "65") (name "Net-(U$30-DO)") (class "Default")
      (node (ref "U$30") (pin "3") (pinfunction "DO_3") (pintype "bidirectional"))
      (node (ref "U$31") (pin "4") (pinfunction "DI_4") (pintype "bidirectional"))
    )
    (net (code "66") (name "Net-(U$31-CO)") (class "Default")
      (node (ref "U$31") (pin "2") (pinfunction "CO_2") (pintype "bidirectional"))
      (node (ref "U$32") (pin "5") (pinfunction "CI_5") (pintype "bidirectional"))
    )
    (net (code "67") (name "Net-(U$31-DO)") (class "Default")
      (node (ref "U$31") (pin "3") (pinfunction "DO_3") (pintype "bidirectional"))
      (node (ref "U$32") (pin "4") (pinfunction "DI_4") (pintype "bidirectional"))
    )
    (net (code "68") (name "Net-(U$32-CO)") (class "Default")
      (node (ref "U$32") (pin "2") (pinfunction "CO_2") (pintype "bidirectional"))
      (node (ref "U$33") (pin "5") (pinfunction "CI_5") (pintype "bidirectional"))
    )
    (net (code "69") (name "Net-(U$32-DO)") (class "Default")
      (node (ref "U$32") (pin "3") (pinfunction "DO_3") (pintype "bidirectional"))
      (node (ref "U$33") (pin "4") (pinfunction "DI_4") (pintype "bidirectional"))
    )
    (net (code "70") (name "Net-(U$33-CO)") (class "Default")
      (node (ref "U$33") (pin "2") (pinfunction "CO_2") (pintype "bidirectional"))
      (node (ref "U$34") (pin "5") (pinfunction "CI_5") (pintype "bidirectional"))
    )
    (net (code "71") (name "Net-(U$33-DO)") (class "Default")
      (node (ref "U$33") (pin "3") (pinfunction "DO_3") (pintype "bidirectional"))
      (node (ref "U$34") (pin "4") (pinfunction "DI_4") (pintype "bidirectional"))
    )
    (net (code "72") (name "Net-(U$34-CO)") (class "Default")
      (node (ref "U$34") (pin "2") (pinfunction "CO_2") (pintype "bidirectional"))
      (node (ref "U$35") (pin "5") (pinfunction "CI_5") (pintype "bidirectional"))
    )
    (net (code "73") (name "Net-(U$34-DO)") (class "Default")
      (node (ref "U$34") (pin "3") (pinfunction "DO_3") (pintype "bidirectional"))
      (node (ref "U$35") (pin "4") (pinfunction "DI_4") (pintype "bidirectional"))
    )
    (net (code "74") (name "Net-(U$35-CO)") (class "Default")
      (node (ref "U$35") (pin "2") (pinfunction "CO_2") (pintype "bidirectional"))
      (node (ref "U$36") (pin "5") (pinfunction "CI_5") (pintype "bidirectional"))
    )
    (net (code "75") (name "Net-(U$35-DO)") (class "Default")
      (node (ref "U$35") (pin "3") (pinfunction "DO_3") (pintype "bidirectional"))
      (node (ref "U$36") (pin "4") (pinfunction "DI_4") (pintype "bidirectional"))
    )
    (net (code "76") (name "Net-(U$36-CO)") (class "Default")
      (node (ref "U$36") (pin "2") (pinfunction "CO_2") (pintype "bidirectional"))
      (node (ref "U$37") (pin "5") (pinfunction "CI_5") (pintype "bidirectional"))
    )
    (net (code "77") (name "Net-(U$36-DO)") (class "Default")
      (node (ref "U$36") (pin "3") (pinfunction "DO_3") (pintype "bidirectional"))
      (node (ref "U$37") (pin "4") (pinfunction "DI_4") (pintype "bidirectional"))
    )
    (net (code "78") (name "Net-(U$37-CO)") (class "Default")
      (node (ref "U$37") (pin "2") (pinfunction "CO_2") (pintype "bidirectional"))
      (node (ref "U$38") (pin "5") (pinfunction "CI_5") (pintype "bidirectional"))
    )
    (net (code "79") (name "Net-(U$37-DO)") (class "Default")
      (node (ref "U$37") (pin "3") (pinfunction "DO_3") (pintype "bidirectional"))
      (node (ref "U$38") (pin "4") (pinfunction "DI_4") (pintype "bidirectional"))
    )
    (net (code "80") (name "Net-(U$38-CO)") (class "Default")
      (node (ref "U$38") (pin "2") (pinfunction "CO_2") (pintype "bidirectional"))
      (node (ref "U$39") (pin "5") (pinfunction "CI_5") (pintype "bidirectional"))
    )
    (net (code "81") (name "Net-(U$38-DO)") (class "Default")
      (node (ref "U$38") (pin "3") (pinfunction "DO_3") (pintype "bidirectional"))
      (node (ref "U$39") (pin "4") (pinfunction "DI_4") (pintype "bidirectional"))
    )
    (net (code "82") (name "Net-(U$39-CO)") (class "Default")
      (node (ref "U$39") (pin "2") (pinfunction "CO_2") (pintype "bidirectional"))
      (node (ref "U$40") (pin "5") (pinfunction "CI_5") (pintype "bidirectional"))
    )
    (net (code "83") (name "Net-(U$39-DO)") (class "Default")
      (node (ref "U$39") (pin "3") (pinfunction "DO_3") (pintype "bidirectional"))
      (node (ref "U$40") (pin "4") (pinfunction "DI_4") (pintype "bidirectional"))
    )
    (net (code "84") (name "Net-(U$40-CO)") (class "Default")
      (node (ref "U$40") (pin "2") (pinfunction "CO_2") (pintype "bidirectional"))
      (node (ref "U$41") (pin "5") (pinfunction "CI_5") (pintype "bidirectional"))
    )
    (net (code "85") (name "Net-(U$40-DO)") (class "Default")
      (node (ref "U$40") (pin "3") (pinfunction "DO_3") (pintype "bidirectional"))
      (node (ref "U$41") (pin "4") (pinfunction "DI_4") (pintype "bidirectional"))
    )
    (net (code "86") (name "Net-(U$41-CO)") (class "Default")
      (node (ref "U$41") (pin "2") (pinfunction "CO_2") (pintype "bidirectional"))
      (node (ref "U$42") (pin "5") (pinfunction "CI_5") (pintype "bidirectional"))
    )
    (net (code "87") (name "Net-(U$41-DO)") (class "Default")
      (node (ref "U$41") (pin "3") (pinfunction "DO_3") (pintype "bidirectional"))
      (node (ref "U$42") (pin "4") (pinfunction "DI_4") (pintype "bidirectional"))
    )
    (net (code "88") (name "Net-(U$42-CO)") (class "Default")
      (node (ref "U$42") (pin "2") (pinfunction "CO_2") (pintype "bidirectional"))
      (node (ref "U$43") (pin "5") (pinfunction "CI_5") (pintype "bidirectional"))
    )
    (net (code "89") (name "Net-(U$42-DO)") (class "Default")
      (node (ref "U$42") (pin "3") (pinfunction "DO_3") (pintype "bidirectional"))
      (node (ref "U$43") (pin "4") (pinfunction "DI_4") (pintype "bidirectional"))
    )
    (net (code "90") (name "Net-(U$43-CO)") (class "Default")
      (node (ref "U$43") (pin "2") (pinfunction "CO_2") (pintype "bidirectional"))
      (node (ref "U$44") (pin "5") (pinfunction "CI_5") (pintype "bidirectional"))
    )
    (net (code "91") (name "Net-(U$43-DO)") (class "Default")
      (node (ref "U$43") (pin "3") (pinfunction "DO_3") (pintype "bidirectional"))
      (node (ref "U$44") (pin "4") (pinfunction "DI_4") (pintype "bidirectional"))
    )
    (net (code "92") (name "Net-(U$44-CO)") (class "Default")
      (node (ref "U$44") (pin "2") (pinfunction "CO_2") (pintype "bidirectional"))
      (node (ref "U$45") (pin "5") (pinfunction "CI_5") (pintype "bidirectional"))
    )
    (net (code "93") (name "Net-(U$44-DO)") (class "Default")
      (node (ref "U$44") (pin "3") (pinfunction "DO_3") (pintype "bidirectional"))
      (node (ref "U$45") (pin "4") (pinfunction "DI_4") (pintype "bidirectional"))
    )
    (net (code "94") (name "Net-(U$45-CO)") (class "Default")
      (node (ref "U$45") (pin "2") (pinfunction "CO_2") (pintype "bidirectional"))
      (node (ref "U$46") (pin "5") (pinfunction "CI_5") (pintype "bidirectional"))
    )
    (net (code "95") (name "Net-(U$45-DO)") (class "Default")
      (node (ref "U$45") (pin "3") (pinfunction "DO_3") (pintype "bidirectional"))
      (node (ref "U$46") (pin "4") (pinfunction "DI_4") (pintype "bidirectional"))
    )
    (net (code "96") (name "Net-(U$46-CO)") (class "Default")
      (node (ref "U$46") (pin "2") (pinfunction "CO_2") (pintype "bidirectional"))
      (node (ref "U$47") (pin "5") (pinfunction "CI_5") (pintype "bidirectional"))
    )
    (net (code "97") (name "Net-(U$46-DO)") (class "Default")
      (node (ref "U$46") (pin "3") (pinfunction "DO_3") (pintype "bidirectional"))
      (node (ref "U$47") (pin "4") (pinfunction "DI_4") (pintype "bidirectional"))
    )
    (net (code "98") (name "Net-(U$47-CO)") (class "Default")
      (node (ref "U$47") (pin "2") (pinfunction "CO_2") (pintype "bidirectional"))
      (node (ref "U$48") (pin "5") (pinfunction "CI_5") (pintype "bidirectional"))
    )
    (net (code "99") (name "Net-(U$47-DO)") (class "Default")
      (node (ref "U$47") (pin "3") (pinfunction "DO_3") (pintype "bidirectional"))
      (node (ref "U$48") (pin "4") (pinfunction "DI_4") (pintype "bidirectional"))
    )
    (net (code "100") (name "Net-(U$48-CO)") (class "Default")
      (node (ref "U$48") (pin "2") (pinfunction "CO_2") (pintype "bidirectional"))
      (node (ref "U$49") (pin "5") (pinfunction "CI_5") (pintype "bidirectional"))
    )
    (net (code "101") (name "Net-(U$48-DO)") (class "Default")
      (node (ref "U$48") (pin "3") (pinfunction "DO_3") (pintype "bidirectional"))
      (node (ref "U$49") (pin "4") (pinfunction "DI_4") (pintype "bidirectional"))
    )
    (net (code "102") (name "Net-(U$49-CO)") (class "Default")
      (node (ref "U$49") (pin "2") (pinfunction "CO_2") (pintype "bidirectional"))
      (node (ref "U$50") (pin "5") (pinfunction "CI_5") (pintype "bidirectional"))
    )
    (net (code "103") (name "Net-(U$49-DO)") (class "Default")
      (node (ref "U$49") (pin "3") (pinfunction "DO_3") (pintype "bidirectional"))
      (node (ref "U$50") (pin "4") (pinfunction "DI_4") (pintype "bidirectional"))
    )
    (net (code "104") (name "Net-(U$50-CO)") (class "Default")
      (node (ref "U$50") (pin "2") (pinfunction "CO_2") (pintype "bidirectional"))
      (node (ref "U$51") (pin "5") (pinfunction "CI_5") (pintype "bidirectional"))
    )
    (net (code "105") (name "Net-(U$50-DO)") (class "Default")
      (node (ref "U$50") (pin "3") (pinfunction "DO_3") (pintype "bidirectional"))
      (node (ref "U$51") (pin "4") (pinfunction "DI_4") (pintype "bidirectional"))
    )
    (net (code "106") (name "Net-(U$51-CO)") (class "Default")
      (node (ref "U$51") (pin "2") (pinfunction "CO_2") (pintype "bidirectional"))
      (node (ref "U$52") (pin "5") (pinfunction "CI_5") (pintype "bidirectional"))
    )
    (net (code "107") (name "Net-(U$51-DO)") (class "Default")
      (node (ref "U$51") (pin "3") (pinfunction "DO_3") (pintype "bidirectional"))
      (node (ref "U$52") (pin "4") (pinfunction "DI_4") (pintype "bidirectional"))
    )
    (net (code "108") (name "Net-(U$52-CO)") (class "Default")
      (node (ref "U$52") (pin "2") (pinfunction "CO_2") (pintype "bidirectional"))
      (node (ref "U$53") (pin "5") (pinfunction "CI_5") (pintype "bidirectional"))
    )
    (net (code "109") (name "Net-(U$52-DO)") (class "Default")
      (node (ref "U$52") (pin "3") (pinfunction "DO_3") (pintype "bidirectional"))
      (node (ref "U$53") (pin "4") (pinfunction "DI_4") (pintype "bidirectional"))
    )
    (net (code "110") (name "Net-(U$53-CO)") (class "Default")
      (node (ref "U$53") (pin "2") (pinfunction "CO_2") (pintype "bidirectional"))
      (node (ref "U$54") (pin "5") (pinfunction "CI_5") (pintype "bidirectional"))
    )
    (net (code "111") (name "Net-(U$53-DO)") (class "Default")
      (node (ref "U$53") (pin "3") (pinfunction "DO_3") (pintype "bidirectional"))
      (node (ref "U$54") (pin "4") (pinfunction "DI_4") (pintype "bidirectional"))
    )
    (net (code "112") (name "Net-(U$54-CO)") (class "Default")
      (node (ref "U$54") (pin "2") (pinfunction "CO_2") (pintype "bidirectional"))
      (node (ref "U$55") (pin "5") (pinfunction "CI_5") (pintype "bidirectional"))
    )
    (net (code "113") (name "Net-(U$54-DO)") (class "Default")
      (node (ref "U$54") (pin "3") (pinfunction "DO_3") (pintype "bidirectional"))
      (node (ref "U$55") (pin "4") (pinfunction "DI_4") (pintype "bidirectional"))
    )
    (net (code "114") (name "Net-(U$55-CO)") (class "Default")
      (node (ref "U$55") (pin "2") (pinfunction "CO_2") (pintype "bidirectional"))
      (node (ref "U$56") (pin "5") (pinfunction "CI_5") (pintype "bidirectional"))
    )
    (net (code "115") (name "Net-(U$55-DO)") (class "Default")
      (node (ref "U$55") (pin "3") (pinfunction "DO_3") (pintype "bidirectional"))
      (node (ref "U$56") (pin "4") (pinfunction "DI_4") (pintype "bidirectional"))
    )
    (net (code "116") (name "Net-(U$56-CO)") (class "Default")
      (node (ref "U$56") (pin "2") (pinfunction "CO_2") (pintype "bidirectional"))
      (node (ref "U$57") (pin "5") (pinfunction "CI_5") (pintype "bidirectional"))
    )
    (net (code "117") (name "Net-(U$56-DO)") (class "Default")
      (node (ref "U$56") (pin "3") (pinfunction "DO_3") (pintype "bidirectional"))
      (node (ref "U$57") (pin "4") (pinfunction "DI_4") (pintype "bidirectional"))
    )
    (net (code "118") (name "Net-(U$57-CO)") (class "Default")
      (node (ref "U$57") (pin "2") (pinfunction "CO_2") (pintype "bidirectional"))
      (node (ref "U$58") (pin "5") (pinfunction "CI_5") (pintype "bidirectional"))
    )
    (net (code "119") (name "Net-(U$57-DO)") (class "Default")
      (node (ref "U$57") (pin "3") (pinfunction "DO_3") (pintype "bidirectional"))
      (node (ref "U$58") (pin "4") (pinfunction "DI_4") (pintype "bidirectional"))
    )
    (net (code "120") (name "Net-(U$58-CO)") (class "Default")
      (node (ref "U$58") (pin "2") (pinfunction "CO_2") (pintype "bidirectional"))
      (node (ref "U$59") (pin "5") (pinfunction "CI_5") (pintype "bidirectional"))
    )
    (net (code "121") (name "Net-(U$58-DO)") (class "Default")
      (node (ref "U$58") (pin "3") (pinfunction "DO_3") (pintype "bidirectional"))
      (node (ref "U$59") (pin "4") (pinfunction "DI_4") (pintype "bidirectional"))
    )
    (net (code "122") (name "Net-(U$59-CO)") (class "Default")
      (node (ref "U$59") (pin "2") (pinfunction "CO_2") (pintype "bidirectional"))
      (node (ref "U$60") (pin "5") (pinfunction "CI_5") (pintype "bidirectional"))
    )
    (net (code "123") (name "Net-(U$59-DO)") (class "Default")
      (node (ref "U$59") (pin "3") (pinfunction "DO_3") (pintype "bidirectional"))
      (node (ref "U$60") (pin "4") (pinfunction "DI_4") (pintype "bidirectional"))
    )
    (net (code "124") (name "Net-(U$60-CO)") (class "Default")
      (node (ref "U$60") (pin "2") (pinfunction "CO_2") (pintype "bidirectional"))
      (node (ref "U$61") (pin "5") (pinfunction "CI_5") (pintype "bidirectional"))
    )
    (net (code "125") (name "Net-(U$60-DO)") (class "Default")
      (node (ref "U$60") (pin "3") (pinfunction "DO_3") (pintype "bidirectional"))
      (node (ref "U$61") (pin "4") (pinfunction "DI_4") (pintype "bidirectional"))
    )
    (net (code "126") (name "Net-(U$61-CO)") (class "Default")
      (node (ref "U$61") (pin "2") (pinfunction "CO_2") (pintype "bidirectional"))
      (node (ref "U$62") (pin "5") (pinfunction "CI_5") (pintype "bidirectional"))
    )
    (net (code "127") (name "Net-(U$61-DO)") (class "Default")
      (node (ref "U$61") (pin "3") (pinfunction "DO_3") (pintype "bidirectional"))
      (node (ref "U$62") (pin "4") (pinfunction "DI_4") (pintype "bidirectional"))
    )
    (net (code "128") (name "Net-(U$62-CO)") (class "Default")
      (node (ref "U$62") (pin "2") (pinfunction "CO_2") (pintype "bidirectional"))
      (node (ref "U$63") (pin "5") (pinfunction "CI_5") (pintype "bidirectional"))
    )
    (net (code "129") (name "Net-(U$62-DO)") (class "Default")
      (node (ref "U$62") (pin "3") (pinfunction "DO_3") (pintype "bidirectional"))
      (node (ref "U$63") (pin "4") (pinfunction "DI_4") (pintype "bidirectional"))
    )
    (net (code "130") (name "Net-(U$63-CO)") (class "Default")
      (node (ref "U$63") (pin "2") (pinfunction "CO_2") (pintype "bidirectional"))
      (node (ref "U$64") (pin "5") (pinfunction "CI_5") (pintype "bidirectional"))
    )
    (net (code "131") (name "Net-(U$63-DO)") (class "Default")
      (node (ref "U$63") (pin "3") (pinfunction "DO_3") (pintype "bidirectional"))
      (node (ref "U$64") (pin "4") (pinfunction "DI_4") (pintype "bidirectional"))
    )
    (net (code "132") (name "Net-(U$64-CO)") (class "Default")
      (node (ref "U$64") (pin "2") (pinfunction "CO_2") (pintype "bidirectional"))
      (node (ref "U$65") (pin "5") (pinfunction "CI_5") (pintype "bidirectional"))
    )
    (net (code "133") (name "Net-(U$64-DO)") (class "Default")
      (node (ref "U$64") (pin "3") (pinfunction "DO_3") (pintype "bidirectional"))
      (node (ref "U$65") (pin "4") (pinfunction "DI_4") (pintype "bidirectional"))
    )
    (net (code "134") (name "Net-(U$65-CO)") (class "Default")
      (node (ref "U$65") (pin "2") (pinfunction "CO_2") (pintype "bidirectional"))
      (node (ref "U$66") (pin "5") (pinfunction "CI_5") (pintype "bidirectional"))
    )
    (net (code "135") (name "Net-(U$65-DO)") (class "Default")
      (node (ref "U$65") (pin "3") (pinfunction "DO_3") (pintype "bidirectional"))
      (node (ref "U$66") (pin "4") (pinfunction "DI_4") (pintype "bidirectional"))
    )
    (net (code "136") (name "Net-(U$66-CO)") (class "Default")
      (node (ref "U$66") (pin "2") (pinfunction "CO_2") (pintype "bidirectional"))
      (node (ref "U$67") (pin "5") (pinfunction "CI_5") (pintype "bidirectional"))
    )
    (net (code "137") (name "Net-(U$66-DO)") (class "Default")
      (node (ref "U$66") (pin "3") (pinfunction "DO_3") (pintype "bidirectional"))
      (node (ref "U$67") (pin "4") (pinfunction "DI_4") (pintype "bidirectional"))
    )
    (net (code "138") (name "Net-(U$67-CO)") (class "Default")
      (node (ref "U$67") (pin "2") (pinfunction "CO_2") (pintype "bidirectional"))
      (node (ref "U$68") (pin "5") (pinfunction "CI_5") (pintype "bidirectional"))
    )
    (net (code "139") (name "Net-(U$67-DO)") (class "Default")
      (node (ref "U$67") (pin "3") (pinfunction "DO_3") (pintype "bidirectional"))
      (node (ref "U$68") (pin "4") (pinfunction "DI_4") (pintype "bidirectional"))
    )
    (net (code "140") (name "Net-(U$68-CO)") (class "Default")
      (node (ref "U$68") (pin "2") (pinfunction "CO_2") (pintype "bidirectional"))
      (node (ref "U$69") (pin "5") (pinfunction "CI_5") (pintype "bidirectional"))
    )
    (net (code "141") (name "Net-(U$68-DO)") (class "Default")
      (node (ref "U$68") (pin "3") (pinfunction "DO_3") (pintype "bidirectional"))
      (node (ref "U$69") (pin "4") (pinfunction "DI_4") (pintype "bidirectional"))
    )
    (net (code "142") (name "Net-(U$69-CO)") (class "Default")
      (node (ref "U$69") (pin "2") (pinfunction "CO_2") (pintype "bidirectional"))
      (node (ref "U$70") (pin "5") (pinfunction "CI_5") (pintype "bidirectional"))
    )
    (net (code "143") (name "Net-(U$69-DO)") (class "Default")
      (node (ref "U$69") (pin "3") (pinfunction "DO_3") (pintype "bidirectional"))
      (node (ref "U$70") (pin "4") (pinfunction "DI_4") (pintype "bidirectional"))
    )
    (net (code "144") (name "Net-(U$70-CO)") (class "Default")
      (node (ref "U$70") (pin "2") (pinfunction "CO_2") (pintype "bidirectional"))
      (node (ref "U$71") (pin "5") (pinfunction "CI_5") (pintype "bidirectional"))
    )
    (net (code "145") (name "Net-(U$70-DO)") (class "Default")
      (node (ref "U$70") (pin "3") (pinfunction "DO_3") (pintype "bidirectional"))
      (node (ref "U$71") (pin "4") (pinfunction "DI_4") (pintype "bidirectional"))
    )
    (net (code "146") (name "Net-(U$71-CO)") (class "Default")
      (node (ref "U$71") (pin "2") (pinfunction "CO_2") (pintype "bidirectional"))
      (node (ref "U$72") (pin "5") (pinfunction "CI_5") (pintype "bidirectional"))
    )
    (net (code "147") (name "Net-(U$71-DO)") (class "Default")
      (node (ref "U$71") (pin "3") (pinfunction "DO_3") (pintype "bidirectional"))
      (node (ref "U$72") (pin "4") (pinfunction "DI_4") (pintype "bidirectional"))
    )
    (net (code "148") (name "Net-(U$72-CO)") (class "Default")
      (node (ref "U$72") (pin "2") (pinfunction "CO_2") (pintype "bidirectional"))
      (node (ref "U$73") (pin "5") (pinfunction "CI_5") (pintype "bidirectional"))
    )
    (net (code "149") (name "Net-(U$72-DO)") (class "Default")
      (node (ref "U$72") (pin "3") (pinfunction "DO_3") (pintype "bidirectional"))
      (node (ref "U$73") (pin "4") (pinfunction "DI_4") (pintype "bidirectional"))
    )
    (net (code "150") (name "Net-(U$73-CO)") (class "Default")
      (node (ref "U$73") (pin "2") (pinfunction "CO_2") (pintype "bidirectional"))
      (node (ref "U$74") (pin "5") (pinfunction "CI_5") (pintype "bidirectional"))
    )
    (net (code "151") (name "Net-(U$73-DO)") (class "Default")
      (node (ref "U$73") (pin "3") (pinfunction "DO_3") (pintype "bidirectional"))
      (node (ref "U$74") (pin "4") (pinfunction "DI_4") (pintype "bidirectional"))
    )
    (net (code "152") (name "Net-(U$74-CO)") (class "Default")
      (node (ref "U$74") (pin "2") (pinfunction "CO_2") (pintype "bidirectional"))
      (node (ref "U$75") (pin "5") (pinfunction "CI_5") (pintype "bidirectional"))
    )
    (net (code "153") (name "Net-(U$74-DO)") (class "Default")
      (node (ref "U$74") (pin "3") (pinfunction "DO_3") (pintype "bidirectional"))
      (node (ref "U$75") (pin "4") (pinfunction "DI_4") (pintype "bidirectional"))
    )
    (net (code "154") (name "Net-(U$75-CO)") (class "Default")
      (node (ref "U$75") (pin "2") (pinfunction "CO_2") (pintype "bidirectional"))
      (node (ref "U$76") (pin "5") (pinfunction "CI_5") (pintype "bidirectional"))
    )
    (net (code "155") (name "Net-(U$75-DO)") (class "Default")
      (node (ref "U$75") (pin "3") (pinfunction "DO_3") (pintype "bidirectional"))
      (node (ref "U$76") (pin "4") (pinfunction "DI_4") (pintype "bidirectional"))
    )
    (net (code "156") (name "Net-(U$76-CO)") (class "Default")
      (node (ref "U$76") (pin "2") (pinfunction "CO_2") (pintype "bidirectional"))
      (node (ref "U$77") (pin "5") (pinfunction "CI_5") (pintype "bidirectional"))
    )
    (net (code "157") (name "Net-(U$76-DO)") (class "Default")
      (node (ref "U$76") (pin "3") (pinfunction "DO_3") (pintype "bidirectional"))
      (node (ref "U$77") (pin "4") (pinfunction "DI_4") (pintype "bidirectional"))
    )
    (net (code "158") (name "Net-(U$77-CO)") (class "Default")
      (node (ref "U$77") (pin "2") (pinfunction "CO_2") (pintype "bidirectional"))
      (node (ref "U$78") (pin "5") (pinfunction "CI_5") (pintype "bidirectional"))
    )
    (net (code "159") (name "Net-(U$77-DO)") (class "Default")
      (node (ref "U$77") (pin "3") (pinfunction "DO_3") (pintype "bidirectional"))
      (node (ref "U$78") (pin "4") (pinfunction "DI_4") (pintype "bidirectional"))
    )
    (net (code "160") (name "unconnected-(IC1-ADJ-Pad1)") (class "Default")
      (node (ref "IC1") (pin "1") (pinfunction "ADJ_1") (pintype "passive"))
    )
    (net (code "161") (name "unconnected-(U$78-CO-Pad2)") (class "Default")
      (node (ref "U$78") (pin "2") (pinfunction "CO_2") (pintype "bidirectional"))
    )
    (net (code "162") (name "unconnected-(U$78-DO-Pad3)") (class "Default")
      (node (ref "U$78") (pin "3") (pinfunction "DO_3") (pintype "bidirectional"))
    )
  )
)
